# LautIO.net
KiCad netlist of a schematic drawn in EAGLE
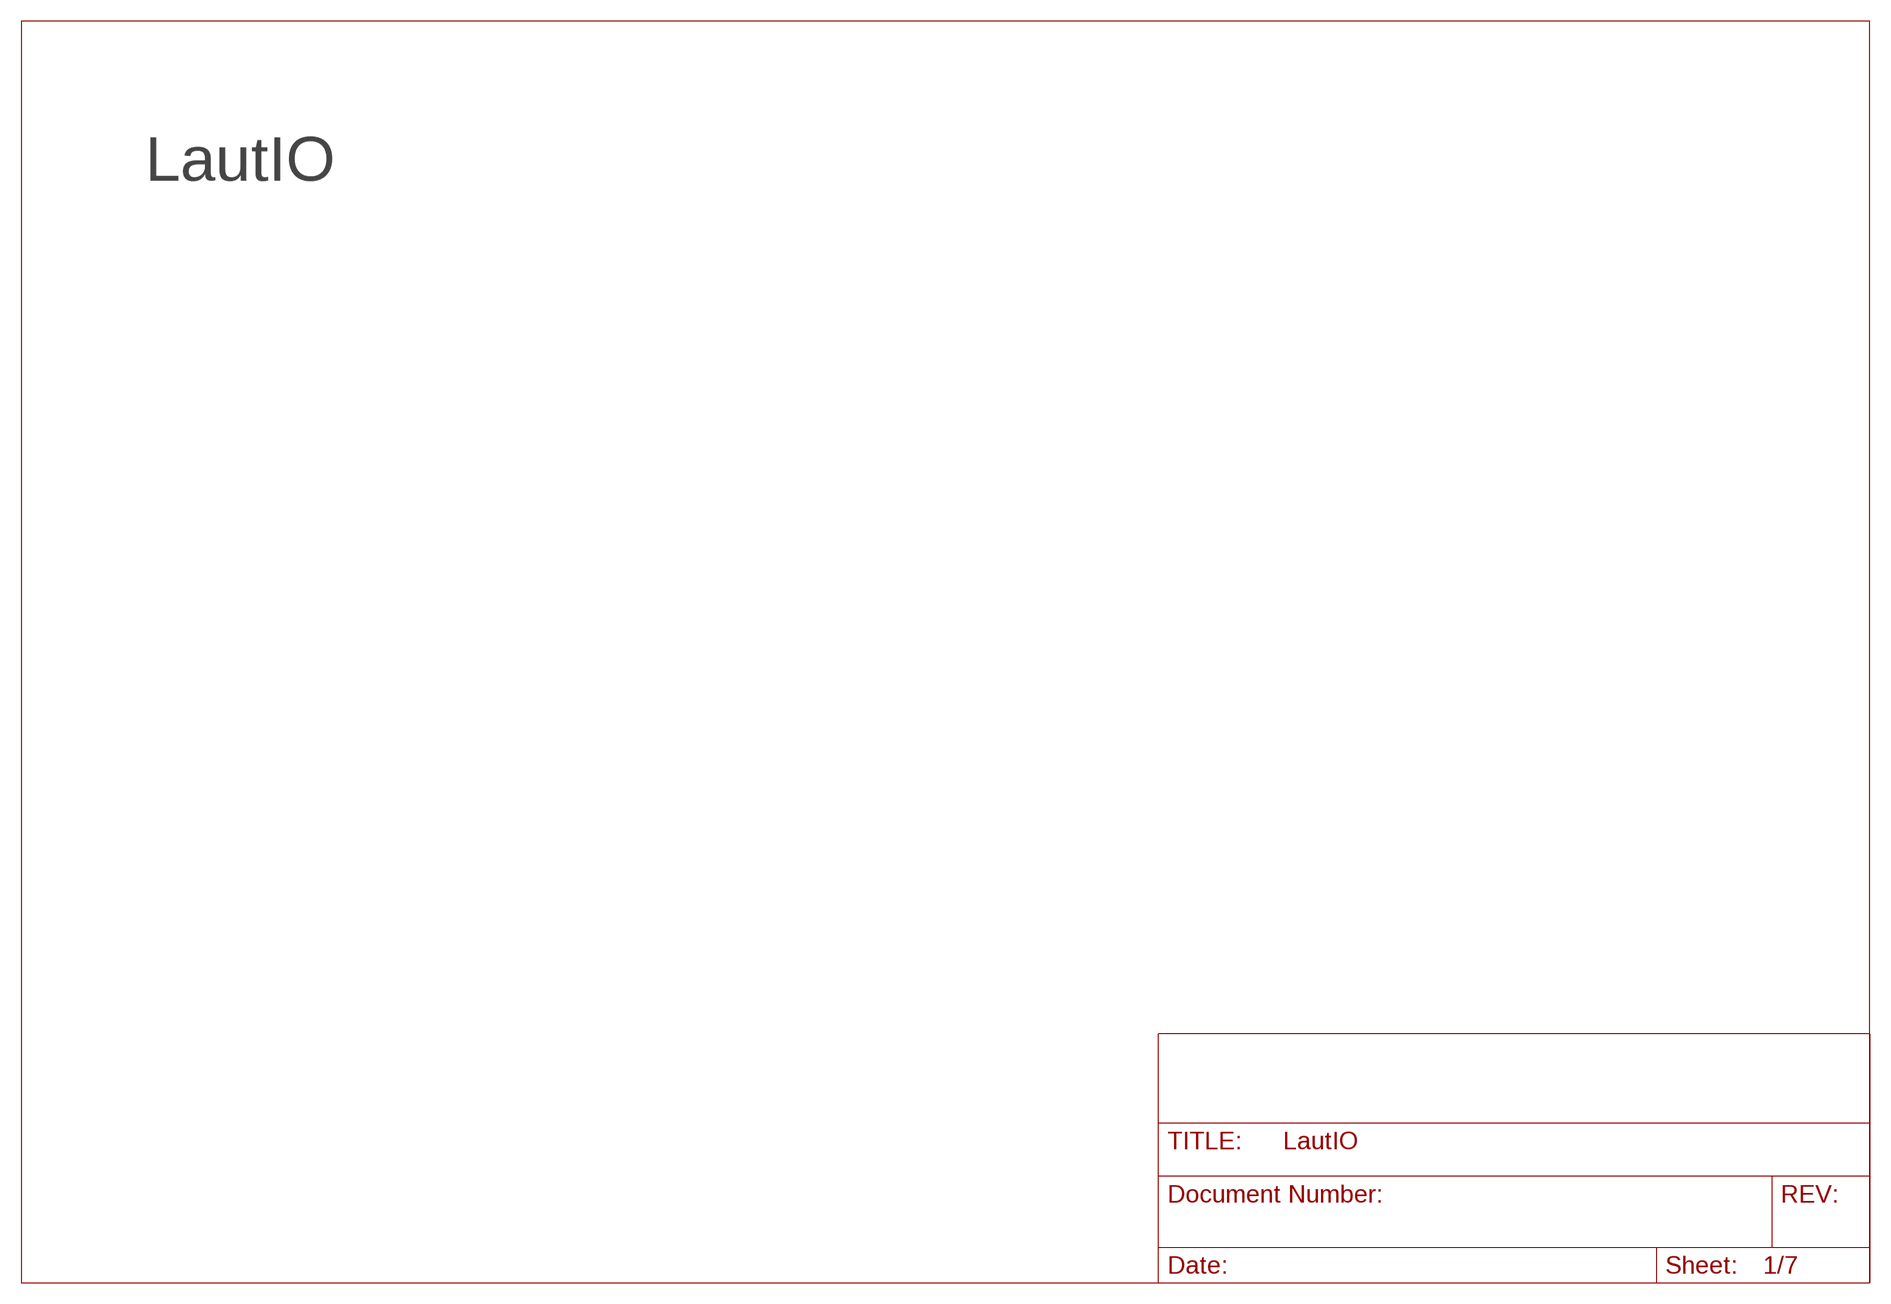
[diagram p0: schematic, sheet 1]
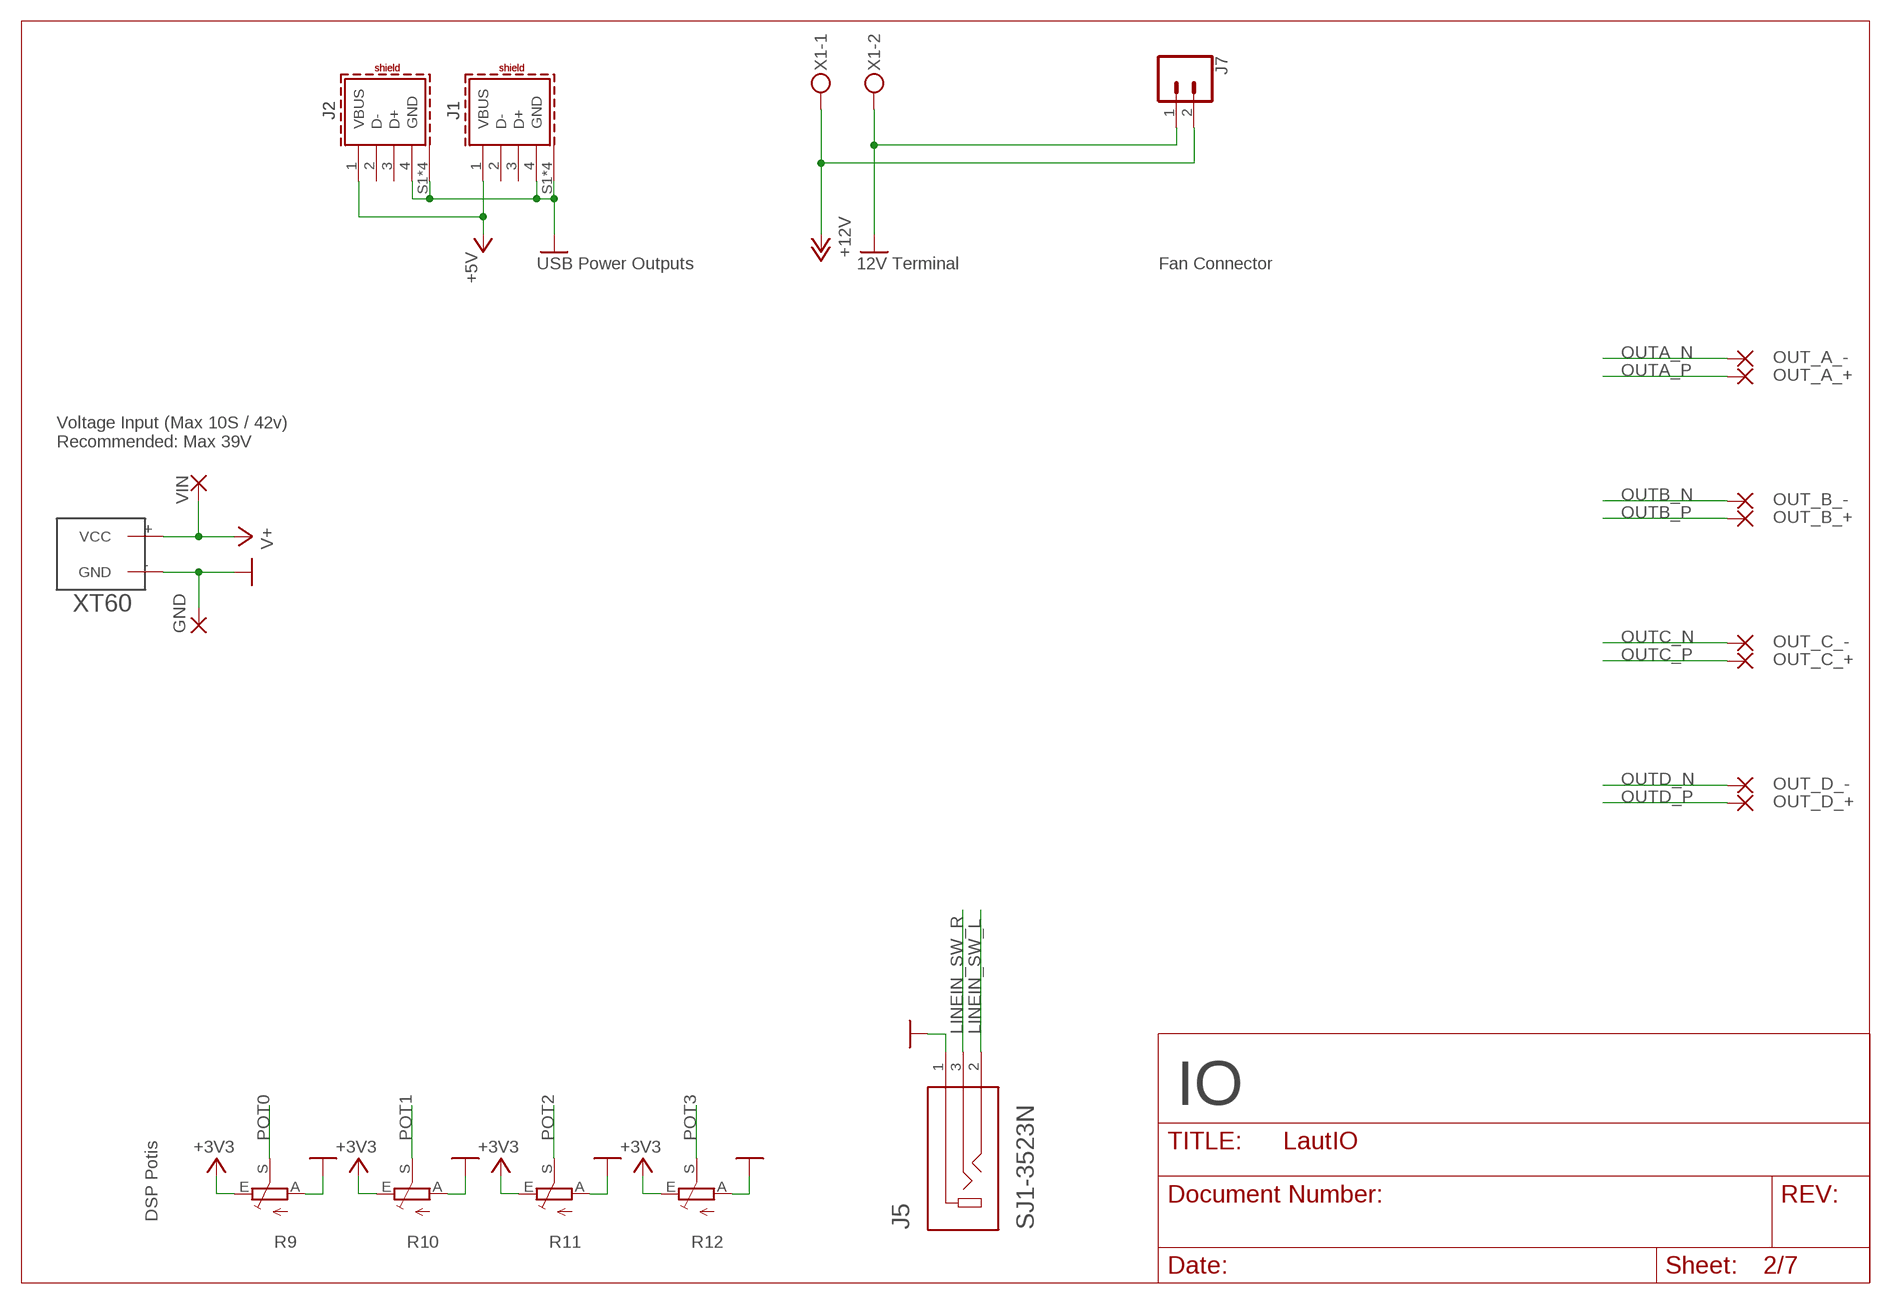
[diagram p1: schematic, sheet 2]
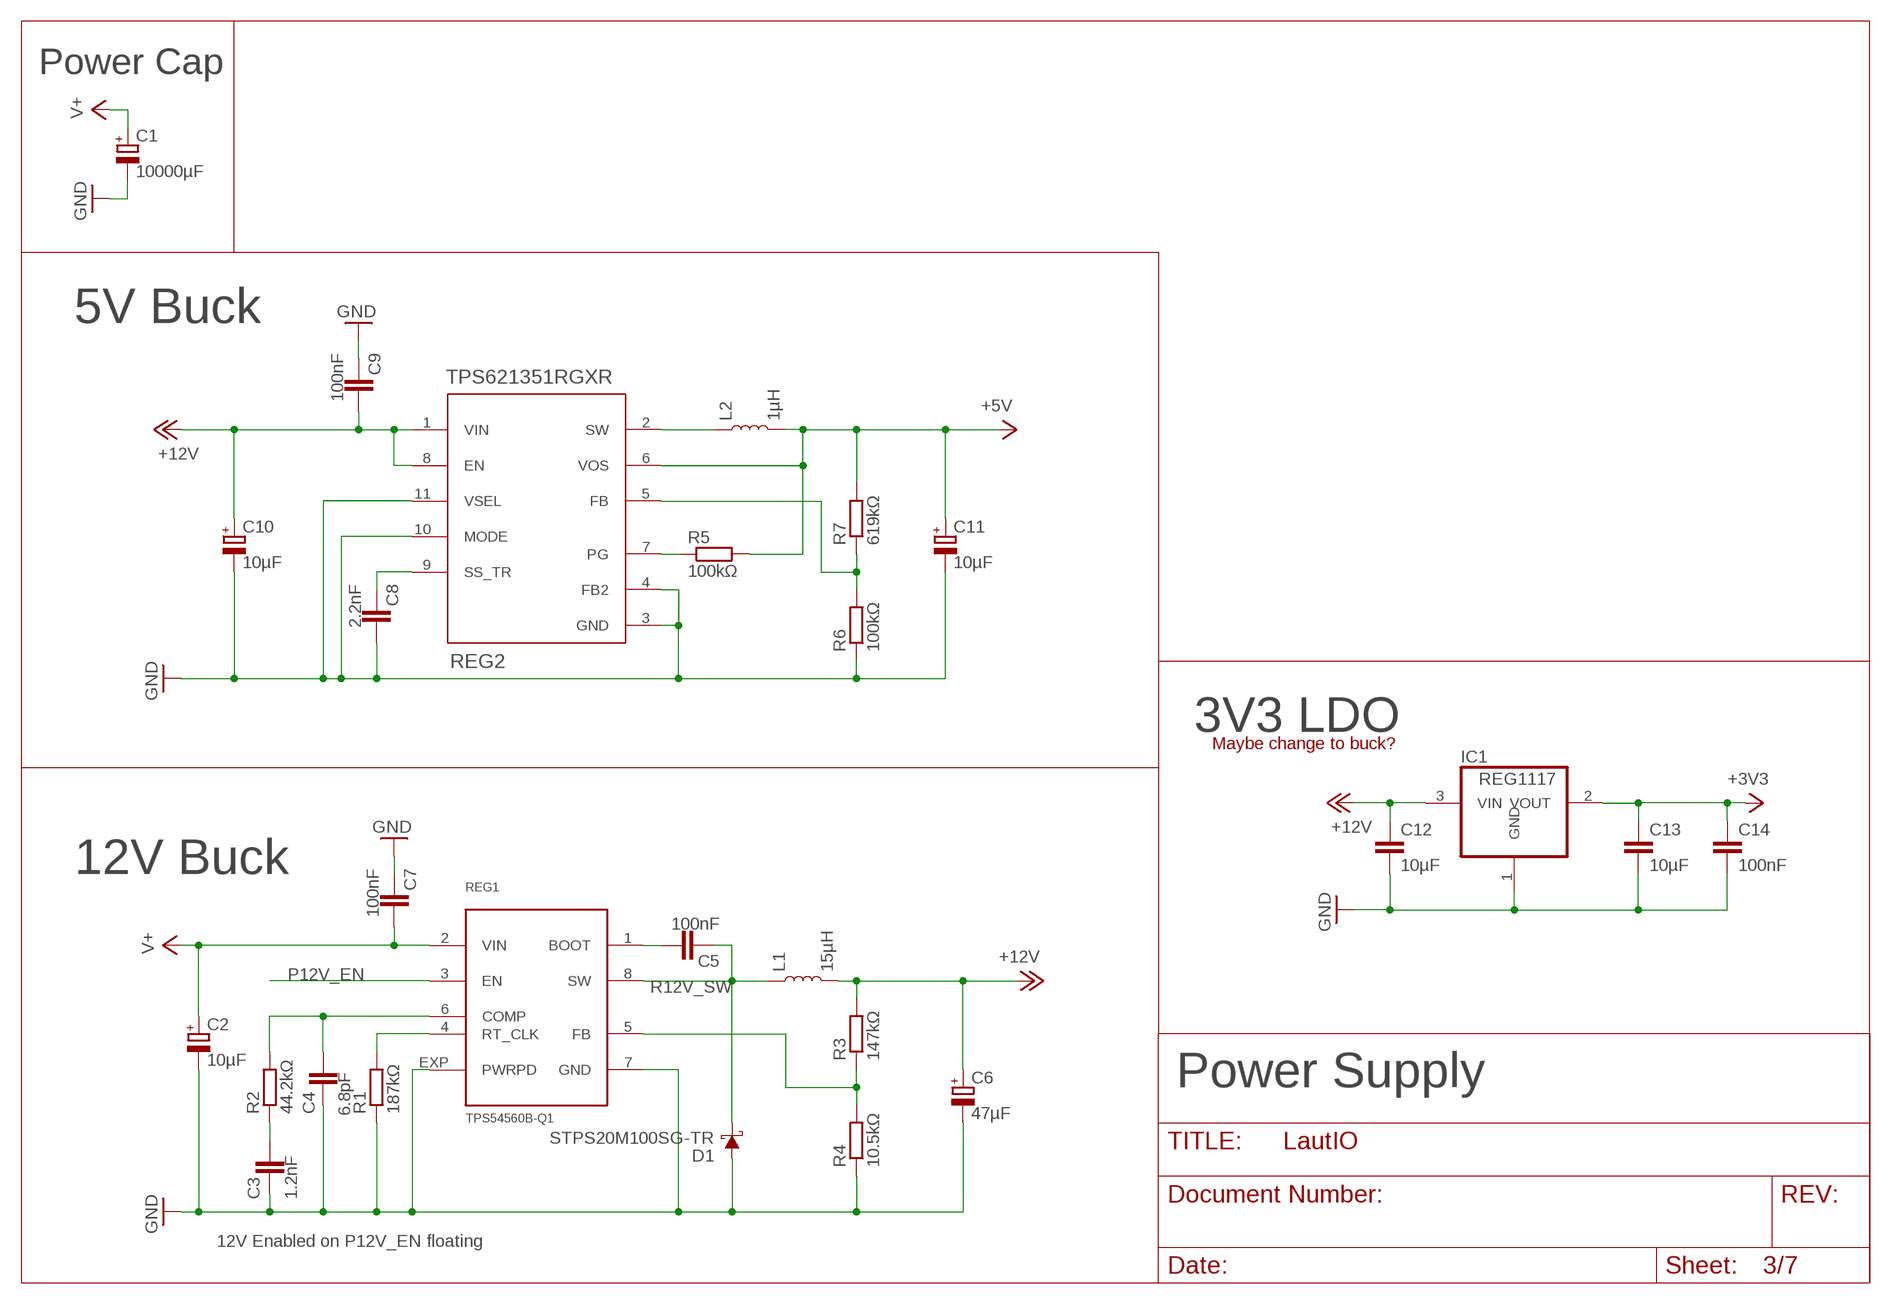
[diagram p2: schematic, sheet 3]
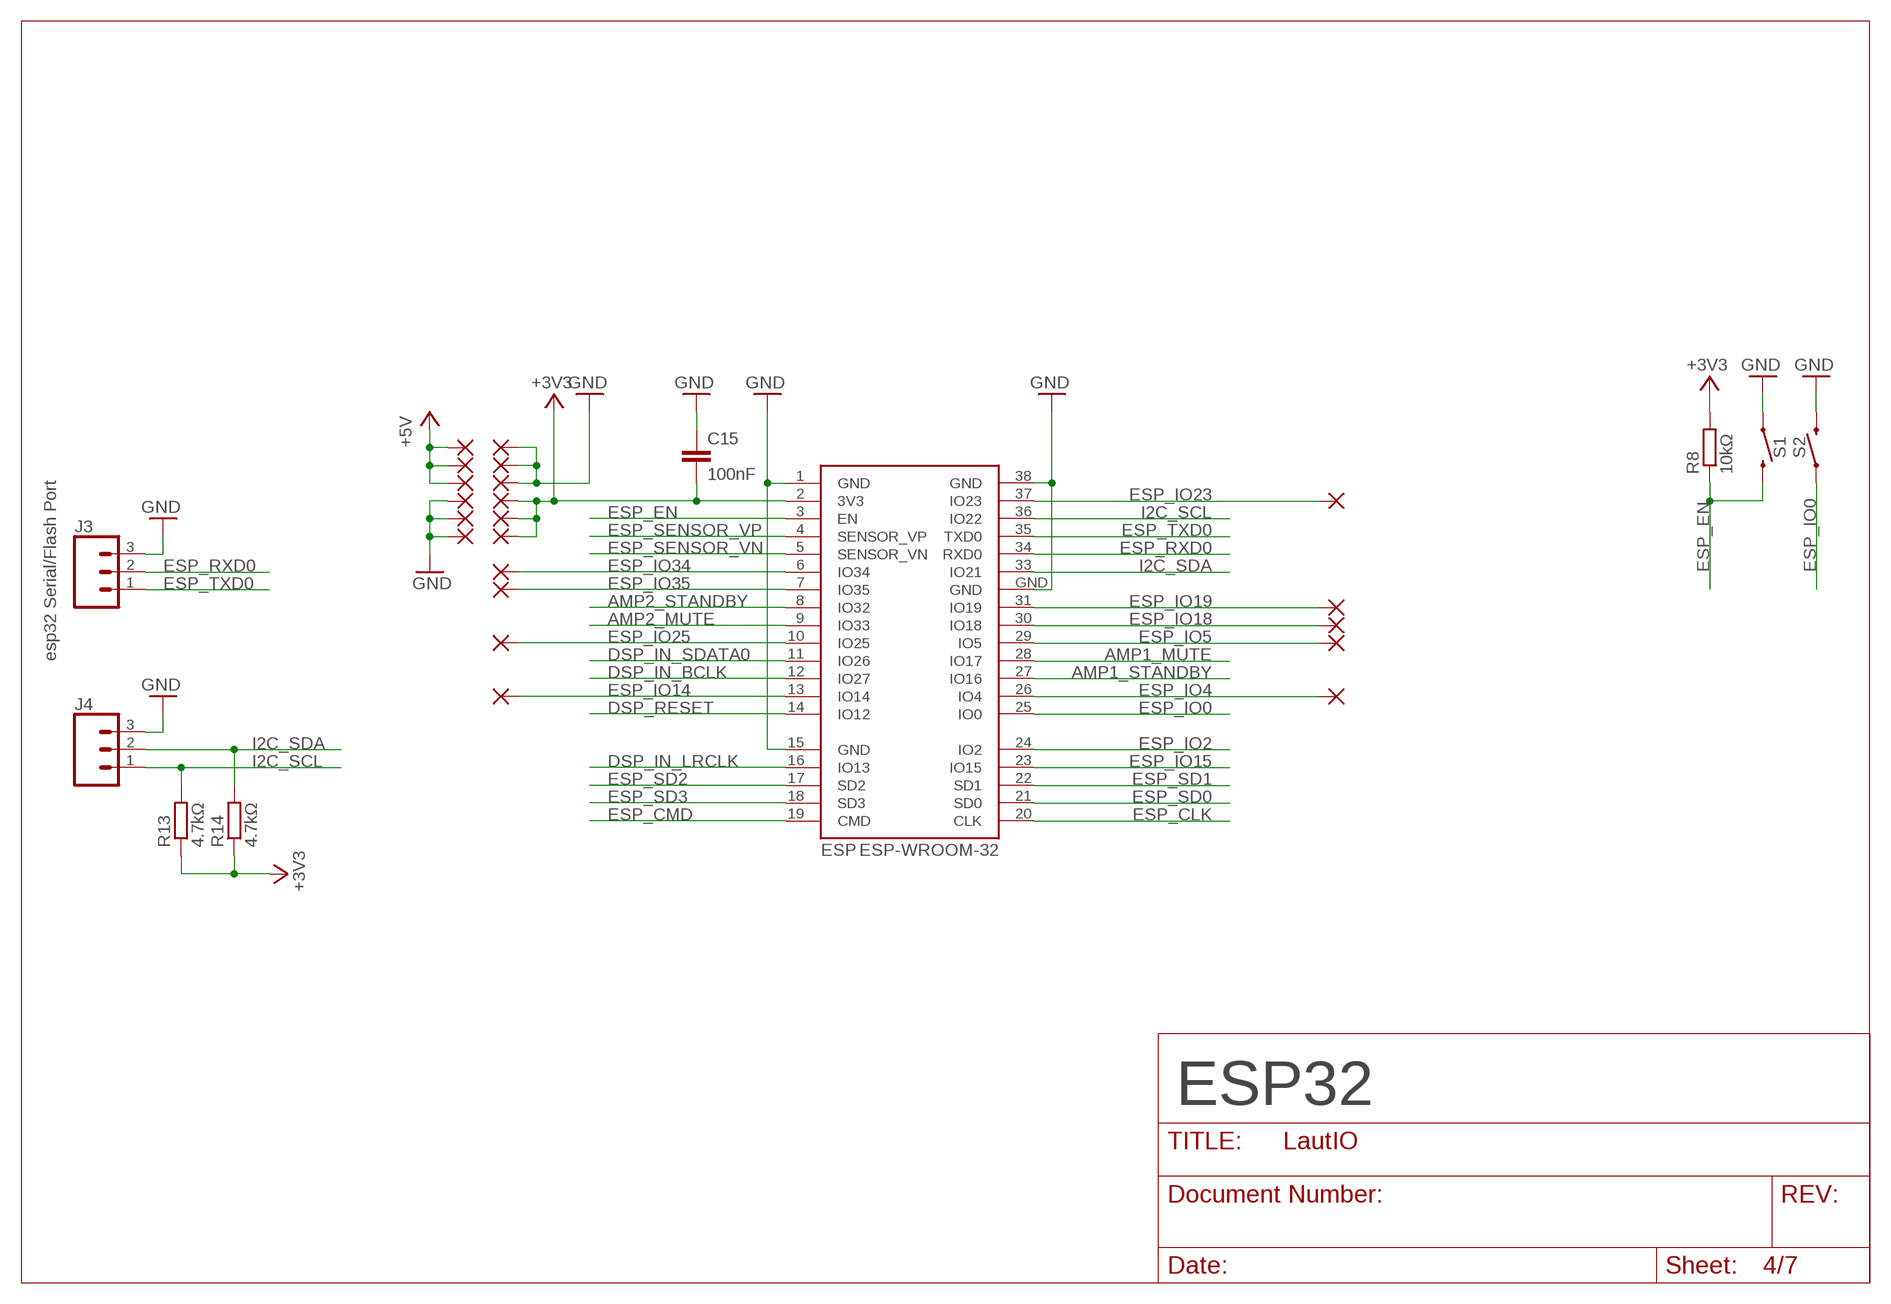
[diagram p3: schematic, sheet 4]
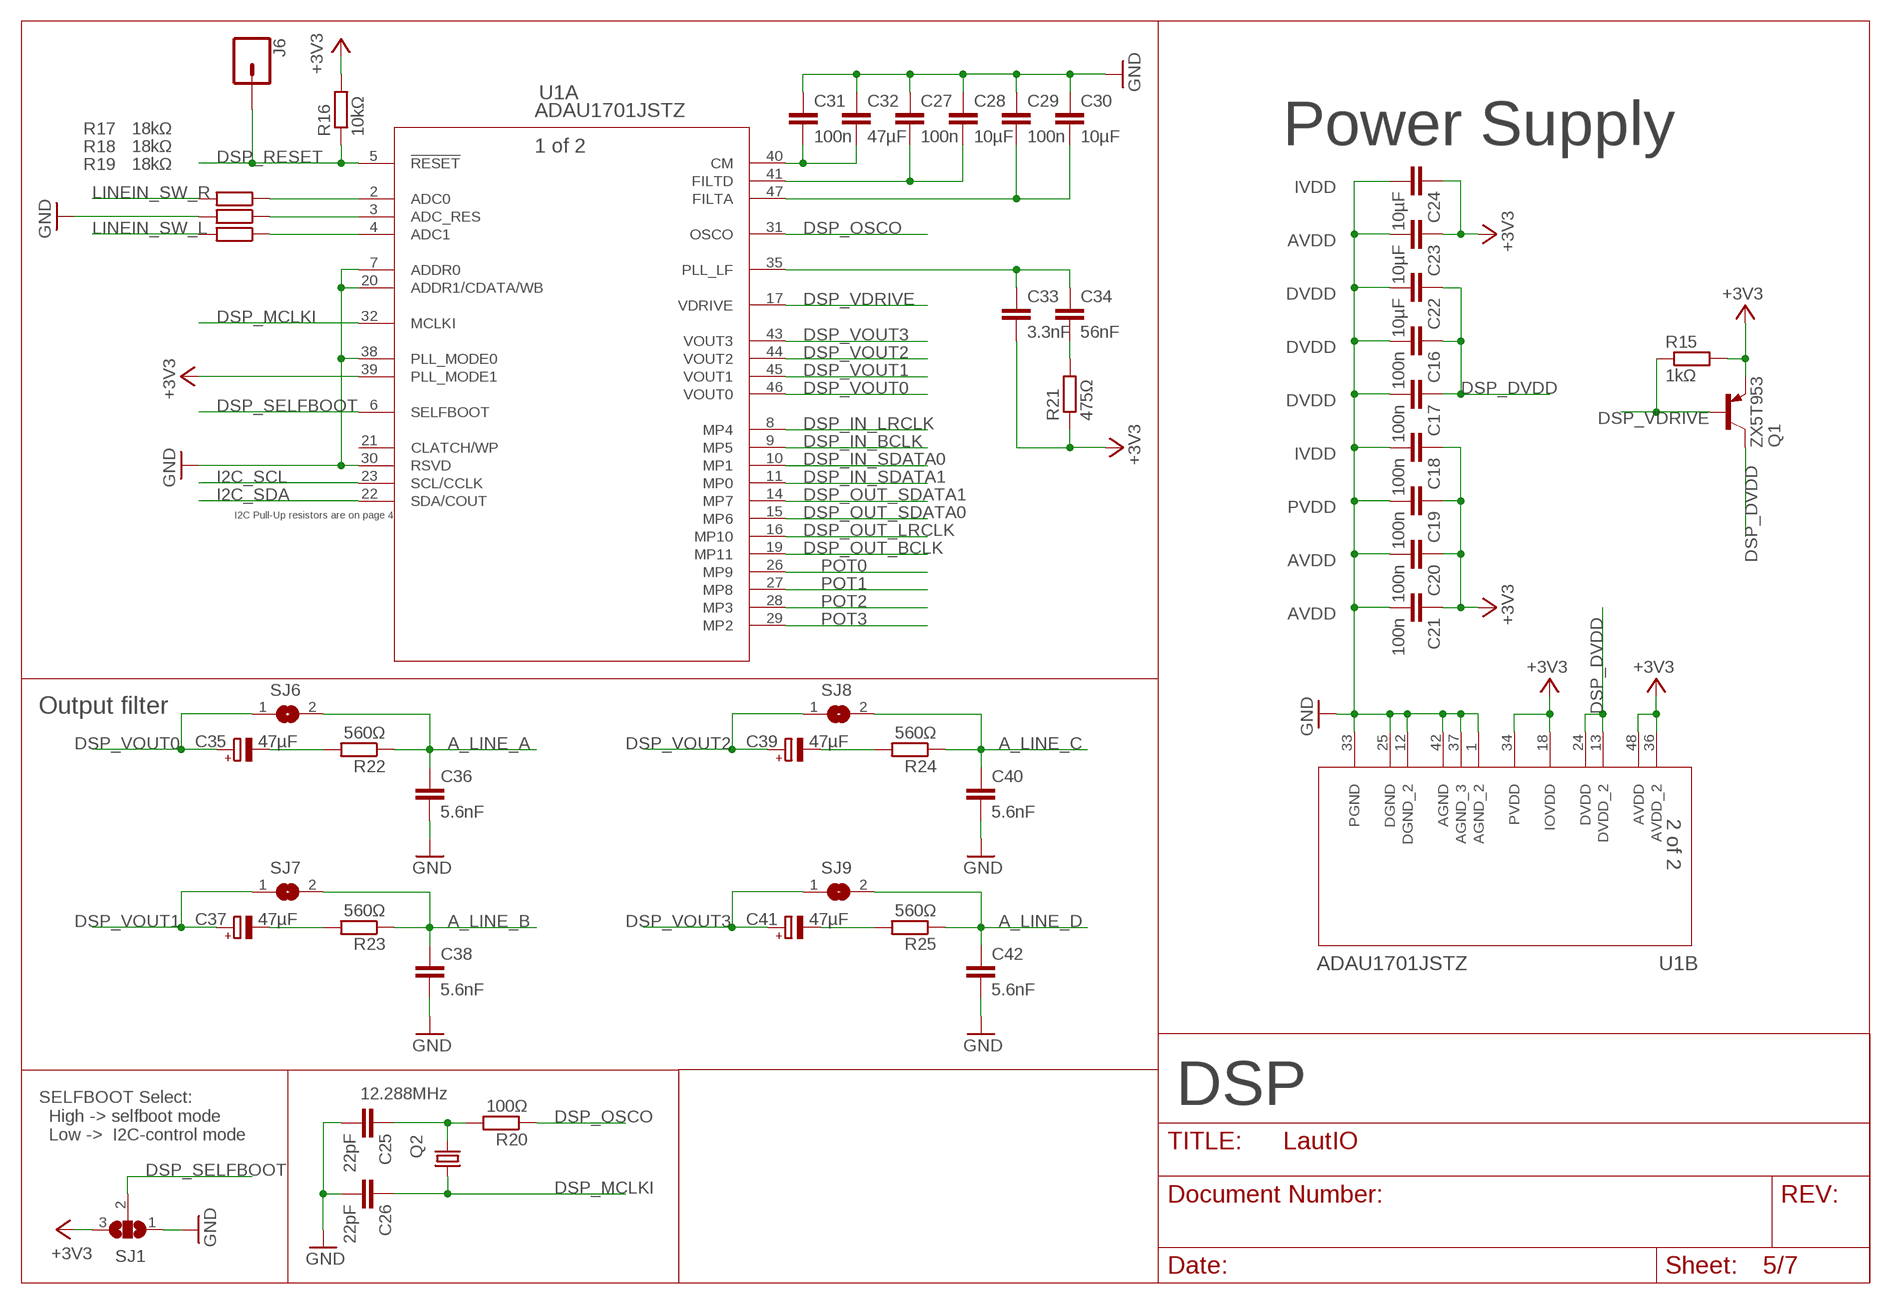
[diagram p4: schematic, sheet 5]
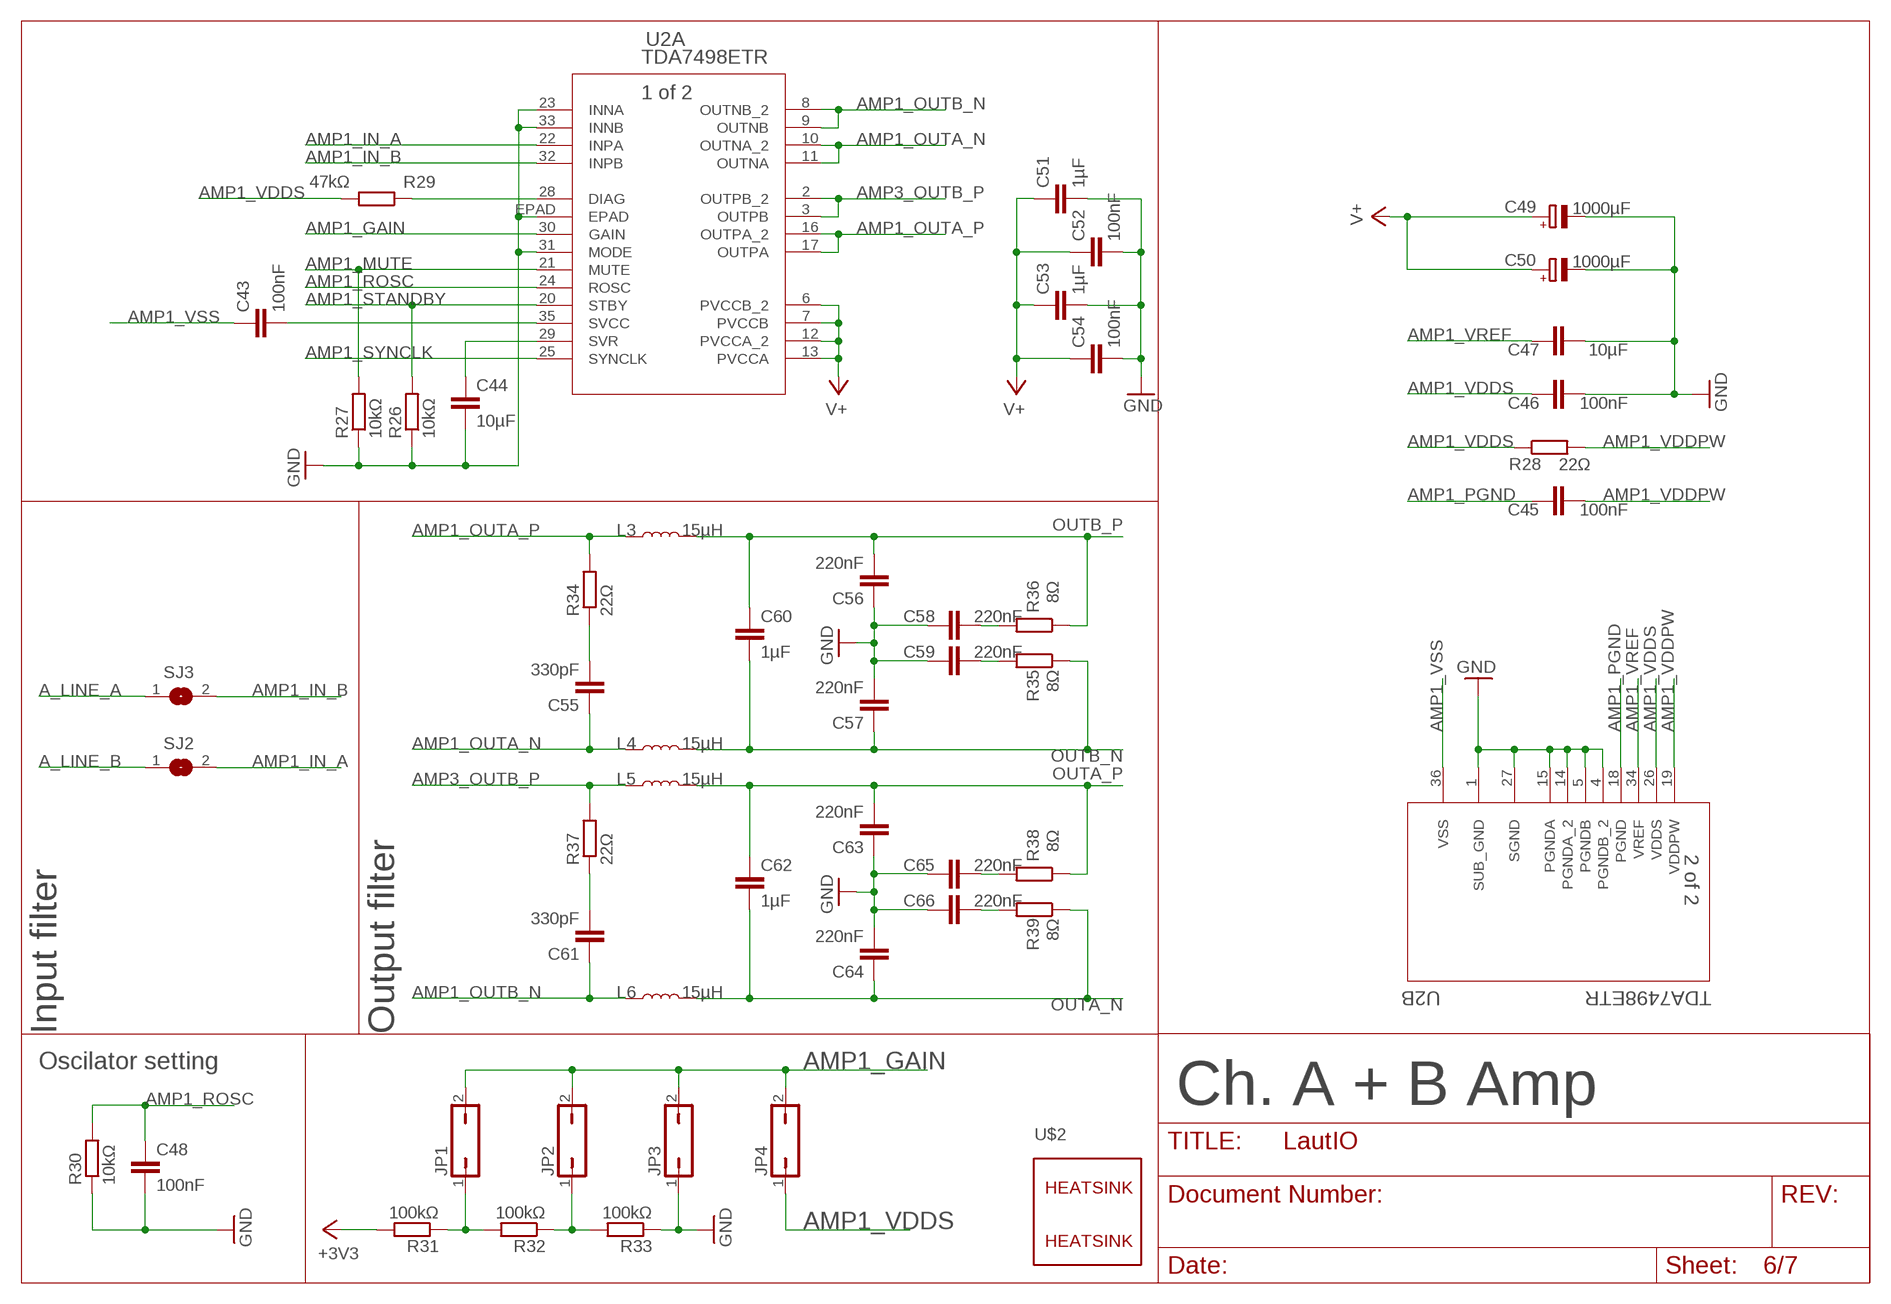
[diagram p5: schematic, sheet 6]
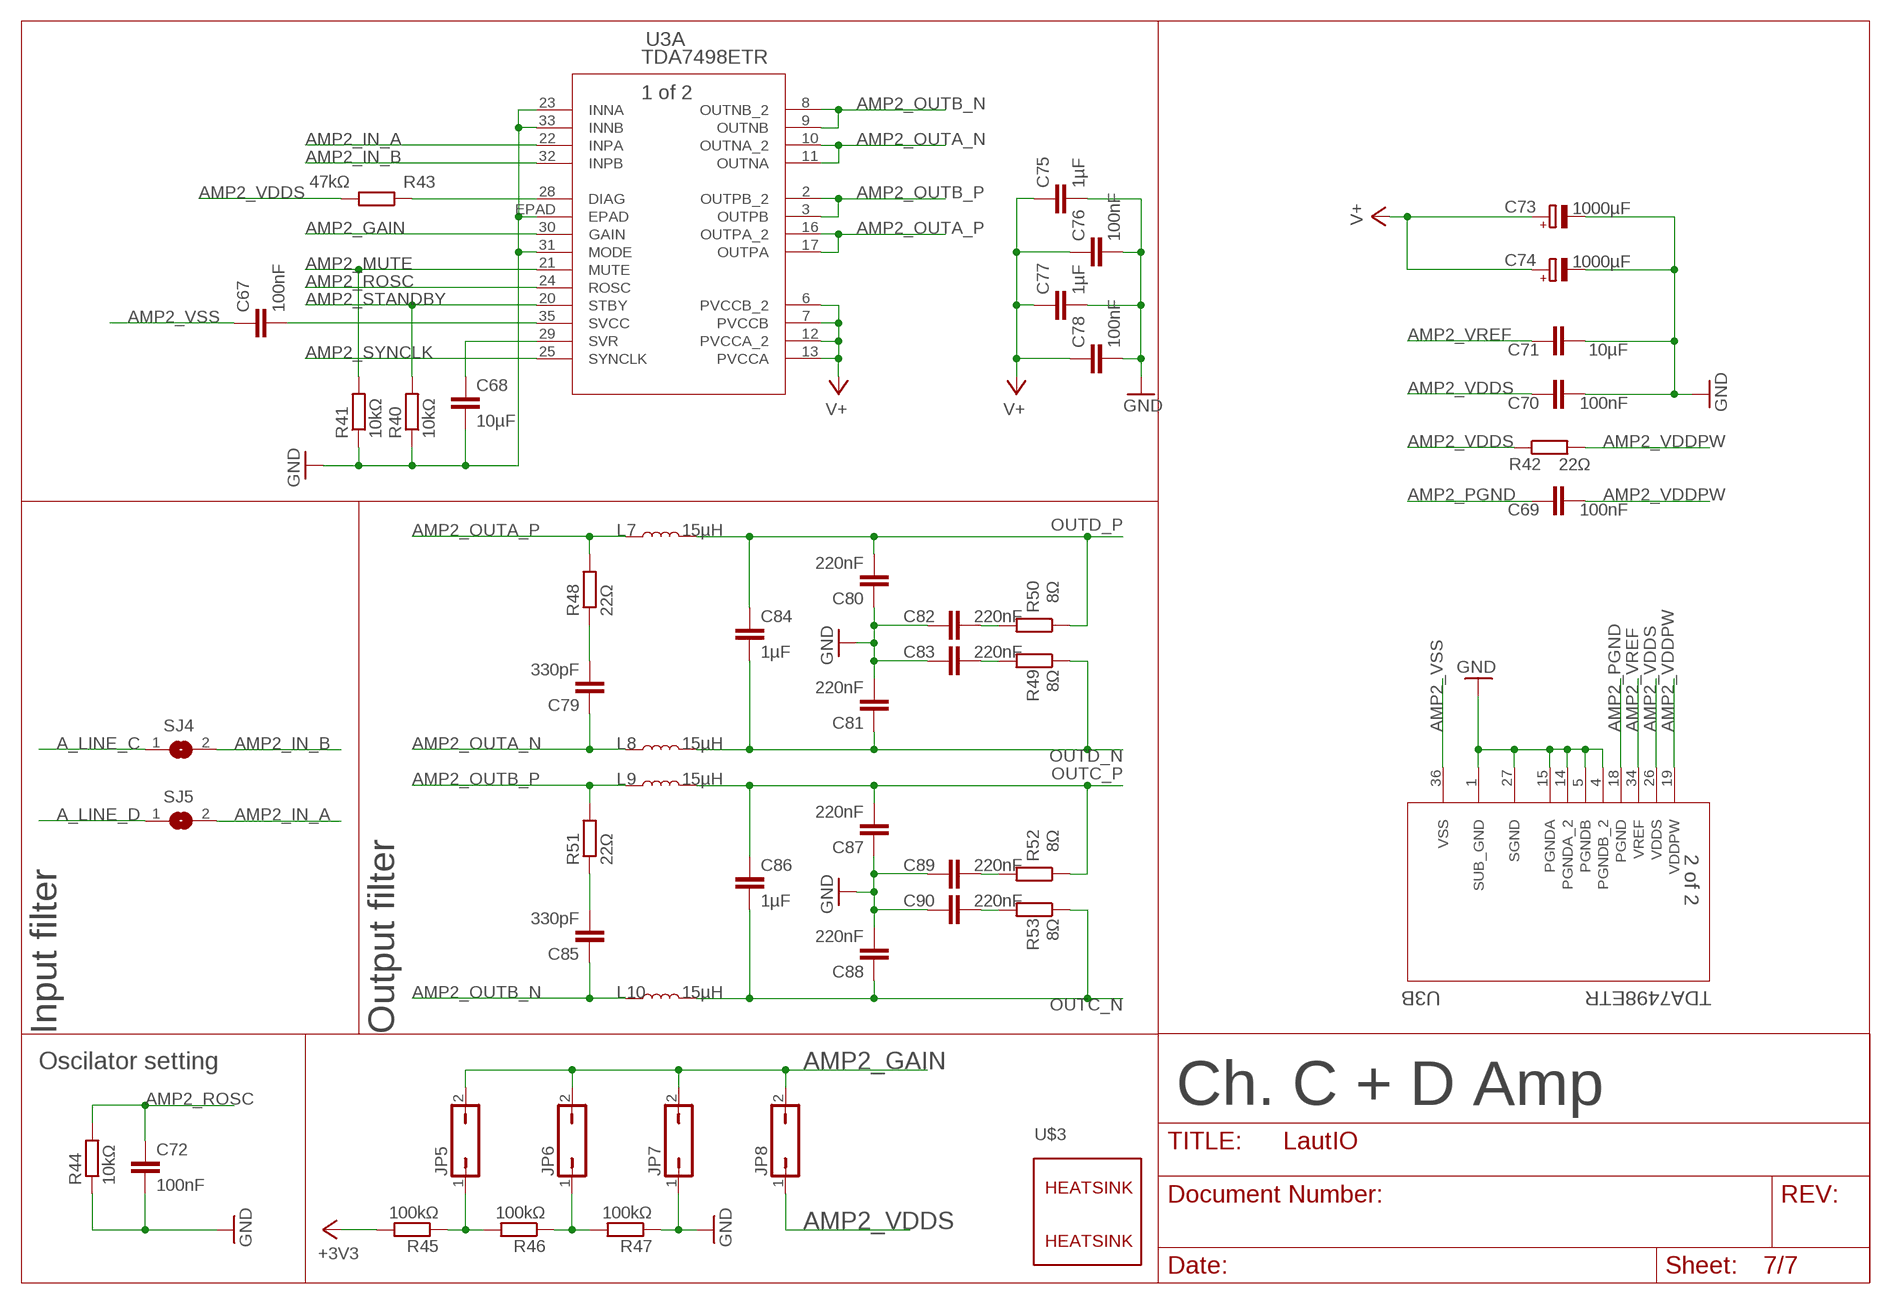
[diagram p6: schematic, sheet 7]

(export (version "E")
  (design (tool "Eeschema 10.0.6"))
  (components
    (comp (ref "C15")
      (value "100nF")
      (footprint "eagle-import:C0603")
      (libsource (lib "eagle-import") (part "C-EUC0603"))
    )
    (comp (ref "ESP")
      (value "ESP-WROOM-32")
      (footprint "eagle-import:ESP-WROOM-32")
      (libsource (lib "eagle-import") (part "ESP-WROOM-32"))
    )
    (comp (ref "IO4")
      (value "SMD2")
      (footprint "eagle-import:SMD1,27-2,54")
      (libsource (lib "eagle-import") (part "SMD2"))
    )
    (comp (ref "IO5")
      (value "SMD2")
      (footprint "eagle-import:SMD1,27-2,54")
      (libsource (lib "eagle-import") (part "SMD2"))
    )
    (comp (ref "IO14")
      (value "SMD2")
      (footprint "eagle-import:SMD1,27-2,54")
      (libsource (lib "eagle-import") (part "SMD2"))
    )
    (comp (ref "IO18")
      (value "SMD2")
      (footprint "eagle-import:SMD1,27-2,54")
      (libsource (lib "eagle-import") (part "SMD2"))
    )
    (comp (ref "IO19")
      (value "SMD2")
      (footprint "eagle-import:SMD1,27-2,54")
      (libsource (lib "eagle-import") (part "SMD2"))
    )
    (comp (ref "IO23")
      (value "SMD2")
      (footprint "eagle-import:SMD1,27-2,54")
      (libsource (lib "eagle-import") (part "SMD2"))
    )
    (comp (ref "IO25")
      (value "SMD2")
      (footprint "eagle-import:SMD1,27-2,54")
      (libsource (lib "eagle-import") (part "SMD2"))
    )
    (comp (ref "IO34")
      (value "SMD2")
      (footprint "eagle-import:SMD1,27-2,54")
      (libsource (lib "eagle-import") (part "SMD2"))
    )
    (comp (ref "IO35")
      (value "SMD2")
      (footprint "eagle-import:SMD1,27-2,54")
      (libsource (lib "eagle-import") (part "SMD2"))
    )
    (comp (ref "J3")
      (value "455-1750-1-ND")
      (footprint "eagle-import:1X03")
      (libsource (lib "eagle-import") (part "CONN_03"))
    )
    (comp (ref "J4")
      (value "455-1750-1-ND")
      (footprint "eagle-import:1X03")
      (libsource (lib "eagle-import") (part "CONN_03"))
    )
    (comp (ref "PAD1")
      (value "SMD2")
      (footprint "eagle-import:SMD1,27-2,54")
      (libsource (lib "eagle-import") (part "SMD2"))
    )
    (comp (ref "PAD2")
      (value "SMD2")
      (footprint "eagle-import:SMD1,27-2,54")
      (libsource (lib "eagle-import") (part "SMD2"))
    )
    (comp (ref "PAD3")
      (value "SMD2")
      (footprint "eagle-import:SMD1,27-2,54")
      (libsource (lib "eagle-import") (part "SMD2"))
    )
    (comp (ref "PAD4")
      (value "SMD2")
      (footprint "eagle-import:SMD1,27-2,54")
      (libsource (lib "eagle-import") (part "SMD2"))
    )
    (comp (ref "PAD5")
      (value "SMD2")
      (footprint "eagle-import:SMD1,27-2,54")
      (libsource (lib "eagle-import") (part "SMD2"))
    )
    (comp (ref "PAD6")
      (value "SMD2")
      (footprint "eagle-import:SMD1,27-2,54")
      (libsource (lib "eagle-import") (part "SMD2"))
    )
    (comp (ref "PAD7")
      (value "SMD2")
      (footprint "eagle-import:SMD1,27-2,54")
      (libsource (lib "eagle-import") (part "SMD2"))
    )
    (comp (ref "PAD8")
      (value "SMD2")
      (footprint "eagle-import:SMD1,27-2,54")
      (libsource (lib "eagle-import") (part "SMD2"))
    )
    (comp (ref "PAD9")
      (value "SMD2")
      (footprint "eagle-import:SMD1,27-2,54")
      (libsource (lib "eagle-import") (part "SMD2"))
    )
    (comp (ref "PAD10")
      (value "SMD2")
      (footprint "eagle-import:SMD1,27-2,54")
      (libsource (lib "eagle-import") (part "SMD2"))
    )
    (comp (ref "PAD11")
      (value "SMD2")
      (footprint "eagle-import:SMD1,27-2,54")
      (libsource (lib "eagle-import") (part "SMD2"))
    )
    (comp (ref "PAD12")
      (value "SMD2")
      (footprint "eagle-import:SMD1,27-2,54")
      (libsource (lib "eagle-import") (part "SMD2"))
    )
    (comp (ref "R8")
      (value "10kΩ")
      (footprint "eagle-import:R0603")
      (libsource (lib "eagle-import") (part "R-EU_R0603"))
    )
    (comp (ref "R13")
      (value "4.7kΩ")
      (footprint "eagle-import:R0603")
      (libsource (lib "eagle-import") (part "R-EU_R0603"))
    )
    (comp (ref "R14")
      (value "4.7kΩ")
      (footprint "eagle-import:R0603")
      (libsource (lib "eagle-import") (part "R-EU_R0603"))
    )
    (comp (ref "S1")
      (value "MOMENTARY-SWITCH-SPST-SMD-6.2MM-TALL")
      (footprint "eagle-import:TACTILE_SWITCH_SMD_6.2MM_TALL")
      (libsource (lib "eagle-import") (part "MOMENTARY-SWITCH-SPST-SMD-6.2MM-TALL"))
    )
    (comp (ref "S2")
      (value "MOMENTARY-SWITCH-SPST-SMD-6.2MM-TALL")
      (footprint "eagle-import:TACTILE_SWITCH_SMD_6.2MM_TALL")
      (libsource (lib "eagle-import") (part "MOMENTARY-SWITCH-SPST-SMD-6.2MM-TALL"))
    )
    (comp (ref "C67")
      (value "100nF")
      (footprint "eagle-import:C0603")
      (libsource (lib "eagle-import") (part "C-EUC0603"))
    )
    (comp (ref "C68")
      (value "10µF")
      (footprint "eagle-import:C1206K")
      (libsource (lib "eagle-import") (part "C-EUC1206K"))
    )
    (comp (ref "C69")
      (value "100nF")
      (footprint "eagle-import:C0603")
      (libsource (lib "eagle-import") (part "C-EUC0603"))
    )
    (comp (ref "C70")
      (value "100nF")
      (footprint "eagle-import:C0603")
      (libsource (lib "eagle-import") (part "C-EUC0603"))
    )
    (comp (ref "C71")
      (value "10µF")
      (footprint "eagle-import:C1206K")
      (libsource (lib "eagle-import") (part "C-EUC1206K"))
    )
    (comp (ref "C72")
      (value "100nF")
      (footprint "eagle-import:C0603")
      (libsource (lib "eagle-import") (part "C-EUC0603"))
    )
    (comp (ref "C73")
      (value "1000µF")
      (footprint "eagle-import:E7,5-16")
      (libsource (lib "eagle-import") (part "CPOL-EUE7.5-16"))
    )
    (comp (ref "C74")
      (value "1000µF")
      (footprint "eagle-import:E7,5-16")
      (libsource (lib "eagle-import") (part "CPOL-EUE7.5-16"))
    )
    (comp (ref "C75")
      (value "1µF")
      (footprint "eagle-import:C0603")
      (libsource (lib "eagle-import") (part "C-EUC0603"))
    )
    (comp (ref "C76")
      (value "100nF")
      (footprint "eagle-import:C0603")
      (libsource (lib "eagle-import") (part "C-EUC0603"))
    )
    (comp (ref "C77")
      (value "1µF")
      (footprint "eagle-import:C0603")
      (libsource (lib "eagle-import") (part "C-EUC0603"))
    )
    (comp (ref "C78")
      (value "100nF")
      (footprint "eagle-import:C0603")
      (libsource (lib "eagle-import") (part "C-EUC0603"))
    )
    (comp (ref "C79")
      (value "330pF")
      (footprint "eagle-import:C0603")
      (libsource (lib "eagle-import") (part "C-EUC0603"))
    )
    (comp (ref "C80")
      (value "220nF")
      (footprint "eagle-import:C0603")
      (libsource (lib "eagle-import") (part "C-EUC0603"))
    )
    (comp (ref "C81")
      (value "220nF")
      (footprint "eagle-import:C0603")
      (libsource (lib "eagle-import") (part "C-EUC0603"))
    )
    (comp (ref "C82")
      (value "220nF")
      (footprint "eagle-import:C0603")
      (libsource (lib "eagle-import") (part "C-EUC0603"))
    )
    (comp (ref "C83")
      (value "220nF")
      (footprint "eagle-import:C0603")
      (libsource (lib "eagle-import") (part "C-EUC0603"))
    )
    (comp (ref "C84")
      (value "1µF")
      (footprint "eagle-import:C3640")
      (libsource (lib "eagle-import") (part "C-EUC3640"))
    )
    (comp (ref "C85")
      (value "330pF")
      (footprint "eagle-import:C0603")
      (libsource (lib "eagle-import") (part "C-EUC0603"))
    )
    (comp (ref "C86")
      (value "1µF")
      (footprint "eagle-import:C3640")
      (libsource (lib "eagle-import") (part "C-EUC3640"))
    )
    (comp (ref "C87")
      (value "220nF")
      (footprint "eagle-import:C0603")
      (libsource (lib "eagle-import") (part "C-EUC0603"))
    )
    (comp (ref "C88")
      (value "220nF")
      (footprint "eagle-import:C0603")
      (libsource (lib "eagle-import") (part "C-EUC0603"))
    )
    (comp (ref "C89")
      (value "220nF")
      (footprint "eagle-import:C0603")
      (libsource (lib "eagle-import") (part "C-EUC0603"))
    )
    (comp (ref "C90")
      (value "220nF")
      (footprint "eagle-import:C0603")
      (libsource (lib "eagle-import") (part "C-EUC0603"))
    )
    (comp (ref "JP5")
      (value "JP1Q")
      (footprint "eagle-import:JP1")
      (libsource (lib "eagle-import") (part "JP1Q"))
    )
    (comp (ref "JP6")
      (value "JP1Q")
      (footprint "eagle-import:JP1")
      (libsource (lib "eagle-import") (part "JP1Q"))
    )
    (comp (ref "JP7")
      (value "JP1Q")
      (footprint "eagle-import:JP1")
      (libsource (lib "eagle-import") (part "JP1Q"))
    )
    (comp (ref "JP8")
      (value "JP1Q")
      (footprint "eagle-import:JP1")
      (libsource (lib "eagle-import") (part "JP1Q"))
    )
    (comp (ref "L7")
      (value "15µH")
      (footprint "eagle-import:INDUCTOR_SDR1307")
      (libsource (lib "eagle-import") (part "INDUCTOR-SDR13-27UH"))
    )
    (comp (ref "L8")
      (value "15µH")
      (footprint "eagle-import:INDUCTOR_SDR1307")
      (libsource (lib "eagle-import") (part "INDUCTOR-SDR13-27UH"))
    )
    (comp (ref "L9")
      (value "15µH")
      (footprint "eagle-import:INDUCTOR_SDR1307")
      (libsource (lib "eagle-import") (part "INDUCTOR-SDR13-27UH"))
    )
    (comp (ref "L10")
      (value "15µH")
      (footprint "eagle-import:INDUCTOR_SDR1307")
      (libsource (lib "eagle-import") (part "INDUCTOR-SDR13-27UH"))
    )
    (comp (ref "R40")
      (value "10kΩ")
      (footprint "eagle-import:R0603")
      (libsource (lib "eagle-import") (part "R-EU_R0603"))
    )
    (comp (ref "R41")
      (value "10kΩ")
      (footprint "eagle-import:R0603")
      (libsource (lib "eagle-import") (part "R-EU_R0603"))
    )
    (comp (ref "R42")
      (value "22Ω")
      (footprint "eagle-import:R0603")
      (libsource (lib "eagle-import") (part "R-EU_R0603"))
    )
    (comp (ref "R43")
      (value "47kΩ")
      (footprint "eagle-import:R0603")
      (libsource (lib "eagle-import") (part "R-EU_R0603"))
    )
    (comp (ref "R44")
      (value "10kΩ")
      (footprint "eagle-import:R0603")
      (libsource (lib "eagle-import") (part "R-EU_R0603"))
    )
    (comp (ref "R45")
      (value "100kΩ")
      (footprint "eagle-import:R0603")
      (libsource (lib "eagle-import") (part "R-EU_R0603"))
    )
    (comp (ref "R46")
      (value "100kΩ")
      (footprint "eagle-import:R0603")
      (libsource (lib "eagle-import") (part "R-EU_R0603"))
    )
    (comp (ref "R47")
      (value "100kΩ")
      (footprint "eagle-import:R0603")
      (libsource (lib "eagle-import") (part "R-EU_R0603"))
    )
    (comp (ref "R48")
      (value "22Ω")
      (footprint "eagle-import:R0603")
      (libsource (lib "eagle-import") (part "R-EU_R0603"))
    )
    (comp (ref "R49")
      (value "8Ω")
      (footprint "eagle-import:R0603")
      (libsource (lib "eagle-import") (part "R-EU_R0603"))
    )
    (comp (ref "R50")
      (value "8Ω")
      (footprint "eagle-import:R0603")
      (libsource (lib "eagle-import") (part "R-EU_R0603"))
    )
    (comp (ref "R51")
      (value "22Ω")
      (footprint "eagle-import:R0603")
      (libsource (lib "eagle-import") (part "R-EU_R0603"))
    )
    (comp (ref "R52")
      (value "8Ω")
      (footprint "eagle-import:R0603")
      (libsource (lib "eagle-import") (part "R-EU_R0603"))
    )
    (comp (ref "R53")
      (value "8Ω")
      (footprint "eagle-import:R0603")
      (libsource (lib "eagle-import") (part "R-EU_R0603"))
    )
    (comp (ref "SJ4") (value "SJ") (footprint "eagle-import:SJ") (libsource (lib "eagle-import") (part "SJ")))
    (comp (ref "SJ5") (value "SJ") (footprint "eagle-import:SJ") (libsource (lib "eagle-import") (part "SJ")))
    (comp (ref "U$3")
      (value "ATS-CPX030030030")
      (footprint "eagle-import:ATS-CPX030030030")
      (libsource (lib "eagle-import") (part "ATS-CPX030030030"))
    )
    (comp (ref "U3")
      (value "TDA7498ETR")
      (footprint "eagle-import:SSO36_TDA7498ETR_STM")
      (fields (field (name "COPYRIGHT") "Copyright (C) 2018 Accelerated Designs. All rights reserved"))
      (libsource (lib "eagle-import") (part "TDA7498ETR"))
    )
    (comp (ref "C43")
      (value "100nF")
      (footprint "eagle-import:C0603")
      (libsource (lib "eagle-import") (part "C-EUC0603"))
    )
    (comp (ref "C44")
      (value "10µF")
      (footprint "eagle-import:C1206K")
      (libsource (lib "eagle-import") (part "C-EUC1206K"))
    )
    (comp (ref "C45")
      (value "100nF")
      (footprint "eagle-import:C0603")
      (libsource (lib "eagle-import") (part "C-EUC0603"))
    )
    (comp (ref "C46")
      (value "100nF")
      (footprint "eagle-import:C0603")
      (libsource (lib "eagle-import") (part "C-EUC0603"))
    )
    (comp (ref "C47")
      (value "10µF")
      (footprint "eagle-import:C1206K")
      (libsource (lib "eagle-import") (part "C-EUC1206K"))
    )
    (comp (ref "C48")
      (value "100nF")
      (footprint "eagle-import:C0603")
      (libsource (lib "eagle-import") (part "C-EUC0603"))
    )
    (comp (ref "C49")
      (value "1000µF")
      (footprint "eagle-import:E7,5-16")
      (libsource (lib "eagle-import") (part "CPOL-EUE7.5-16"))
    )
    (comp (ref "C50")
      (value "1000µF")
      (footprint "eagle-import:E7,5-16")
      (libsource (lib "eagle-import") (part "CPOL-EUE7.5-16"))
    )
    (comp (ref "C51")
      (value "1µF")
      (footprint "eagle-import:C0603")
      (libsource (lib "eagle-import") (part "C-EUC0603"))
    )
    (comp (ref "C52")
      (value "100nF")
      (footprint "eagle-import:C0603")
      (libsource (lib "eagle-import") (part "C-EUC0603"))
    )
    (comp (ref "C53")
      (value "1µF")
      (footprint "eagle-import:C0603")
      (libsource (lib "eagle-import") (part "C-EUC0603"))
    )
    (comp (ref "C54")
      (value "100nF")
      (footprint "eagle-import:C0603")
      (libsource (lib "eagle-import") (part "C-EUC0603"))
    )
    (comp (ref "C55")
      (value "330pF")
      (footprint "eagle-import:C0603")
      (libsource (lib "eagle-import") (part "C-EUC0603"))
    )
    (comp (ref "C56")
      (value "220nF")
      (footprint "eagle-import:C0603")
      (libsource (lib "eagle-import") (part "C-EUC0603"))
    )
    (comp (ref "C57")
      (value "220nF")
      (footprint "eagle-import:C0603")
      (libsource (lib "eagle-import") (part "C-EUC0603"))
    )
    (comp (ref "C58")
      (value "220nF")
      (footprint "eagle-import:C0603")
      (libsource (lib "eagle-import") (part "C-EUC0603"))
    )
    (comp (ref "C59")
      (value "220nF")
      (footprint "eagle-import:C0603")
      (libsource (lib "eagle-import") (part "C-EUC0603"))
    )
    (comp (ref "C60")
      (value "1µF")
      (footprint "eagle-import:C3640")
      (libsource (lib "eagle-import") (part "C-EUC3640"))
    )
    (comp (ref "C61")
      (value "330pF")
      (footprint "eagle-import:C0603")
      (libsource (lib "eagle-import") (part "C-EUC0603"))
    )
    (comp (ref "C62")
      (value "1µF")
      (footprint "eagle-import:C3640")
      (libsource (lib "eagle-import") (part "C-EUC3640"))
    )
    (comp (ref "C63")
      (value "220nF")
      (footprint "eagle-import:C0603")
      (libsource (lib "eagle-import") (part "C-EUC0603"))
    )
    (comp (ref "C64")
      (value "220nF")
      (footprint "eagle-import:C0603")
      (libsource (lib "eagle-import") (part "C-EUC0603"))
    )
    (comp (ref "C65")
      (value "220nF")
      (footprint "eagle-import:C0603")
      (libsource (lib "eagle-import") (part "C-EUC0603"))
    )
    (comp (ref "C66")
      (value "220nF")
      (footprint "eagle-import:C0603")
      (libsource (lib "eagle-import") (part "C-EUC0603"))
    )
    (comp (ref "JP1")
      (value "JP1Q")
      (footprint "eagle-import:JP1")
      (libsource (lib "eagle-import") (part "JP1Q"))
    )
    (comp (ref "JP2")
      (value "JP1Q")
      (footprint "eagle-import:JP1")
      (libsource (lib "eagle-import") (part "JP1Q"))
    )
    (comp (ref "JP3")
      (value "JP1Q")
      (footprint "eagle-import:JP1")
      (libsource (lib "eagle-import") (part "JP1Q"))
    )
    (comp (ref "JP4")
      (value "JP1Q")
      (footprint "eagle-import:JP1")
      (libsource (lib "eagle-import") (part "JP1Q"))
    )
    (comp (ref "L3")
      (value "15µH")
      (footprint "eagle-import:INDUCTOR_SDR1307")
      (libsource (lib "eagle-import") (part "INDUCTOR-SDR13-27UH"))
    )
    (comp (ref "L4")
      (value "15µH")
      (footprint "eagle-import:INDUCTOR_SDR1307")
      (libsource (lib "eagle-import") (part "INDUCTOR-SDR13-27UH"))
    )
    (comp (ref "L5")
      (value "15µH")
      (footprint "eagle-import:INDUCTOR_SDR1307")
      (libsource (lib "eagle-import") (part "INDUCTOR-SDR13-27UH"))
    )
    (comp (ref "L6")
      (value "15µH")
      (footprint "eagle-import:INDUCTOR_SDR1307")
      (libsource (lib "eagle-import") (part "INDUCTOR-SDR13-27UH"))
    )
    (comp (ref "R26")
      (value "10kΩ")
      (footprint "eagle-import:R0603")
      (libsource (lib "eagle-import") (part "R-EU_R0603"))
    )
    (comp (ref "R27")
      (value "10kΩ")
      (footprint "eagle-import:R0603")
      (libsource (lib "eagle-import") (part "R-EU_R0603"))
    )
    (comp (ref "R28")
      (value "22Ω")
      (footprint "eagle-import:R0603")
      (libsource (lib "eagle-import") (part "R-EU_R0603"))
    )
    (comp (ref "R29")
      (value "47kΩ")
      (footprint "eagle-import:R0603")
      (libsource (lib "eagle-import") (part "R-EU_R0603"))
    )
    (comp (ref "R30")
      (value "10kΩ")
      (footprint "eagle-import:R0603")
      (libsource (lib "eagle-import") (part "R-EU_R0603"))
    )
    (comp (ref "R31")
      (value "100kΩ")
      (footprint "eagle-import:R0603")
      (libsource (lib "eagle-import") (part "R-EU_R0603"))
    )
    (comp (ref "R32")
      (value "100kΩ")
      (footprint "eagle-import:R0603")
      (libsource (lib "eagle-import") (part "R-EU_R0603"))
    )
    (comp (ref "R33")
      (value "100kΩ")
      (footprint "eagle-import:R0603")
      (libsource (lib "eagle-import") (part "R-EU_R0603"))
    )
    (comp (ref "R34")
      (value "22Ω")
      (footprint "eagle-import:R0603")
      (libsource (lib "eagle-import") (part "R-EU_R0603"))
    )
    (comp (ref "R35")
      (value "8Ω")
      (footprint "eagle-import:R0603")
      (libsource (lib "eagle-import") (part "R-EU_R0603"))
    )
    (comp (ref "R36")
      (value "8Ω")
      (footprint "eagle-import:R0603")
      (libsource (lib "eagle-import") (part "R-EU_R0603"))
    )
    (comp (ref "R37")
      (value "22Ω")
      (footprint "eagle-import:R0603")
      (libsource (lib "eagle-import") (part "R-EU_R0603"))
    )
    (comp (ref "R38")
      (value "8Ω")
      (footprint "eagle-import:R0603")
      (libsource (lib "eagle-import") (part "R-EU_R0603"))
    )
    (comp (ref "R39")
      (value "8Ω")
      (footprint "eagle-import:R0603")
      (libsource (lib "eagle-import") (part "R-EU_R0603"))
    )
    (comp (ref "SJ2") (value "SJ") (footprint "eagle-import:SJ") (libsource (lib "eagle-import") (part "SJ")))
    (comp (ref "SJ3") (value "SJ") (footprint "eagle-import:SJ") (libsource (lib "eagle-import") (part "SJ")))
    (comp (ref "U$2")
      (value "ATS-CPX030030030")
      (footprint "eagle-import:ATS-CPX030030030")
      (libsource (lib "eagle-import") (part "ATS-CPX030030030"))
    )
    (comp (ref "U2")
      (value "TDA7498ETR")
      (footprint "eagle-import:SSO36_TDA7498ETR_STM")
      (fields (field (name "COPYRIGHT") "Copyright (C) 2018 Accelerated Designs. All rights reserved"))
      (libsource (lib "eagle-import") (part "TDA7498ETR"))
    )
    (comp (ref "GND")
      (value "SMD5")
      (footprint "eagle-import:SMD2,54-5,08")
      (libsource (lib "eagle-import") (part "SMD5"))
    )
    (comp (ref "J1")
      (value "614004134726")
      (footprint "eagle-import:614004134726")
      (libsource (lib "eagle-import") (part "614004134726"))
    )
    (comp (ref "J2")
      (value "614004134726")
      (footprint "eagle-import:614004134726")
      (libsource (lib "eagle-import") (part "614004134726"))
    )
    (comp (ref "J5")
      (value "SJ1-3523N")
      (footprint "eagle-import:CUI_SJ1-3523N")
      (fields (field (name "MANUFACTURER") "CUI"))
      (libsource (lib "eagle-import") (part "SJ1-3523N"))
    )
    (comp (ref "J7")
      (value "CONN_02")
      (footprint "eagle-import:1X02")
      (libsource (lib "eagle-import") (part "CONN_02"))
    )
    (comp (ref "OUT_A_+")
      (value "SMD2")
      (footprint "eagle-import:SMD1,27-2,54")
      (libsource (lib "eagle-import") (part "SMD2"))
    )
    (comp (ref "OUT_A_-")
      (value "SMD2")
      (footprint "eagle-import:SMD1,27-2,54")
      (libsource (lib "eagle-import") (part "SMD2"))
    )
    (comp (ref "OUT_B_+")
      (value "SMD2")
      (footprint "eagle-import:SMD1,27-2,54")
      (libsource (lib "eagle-import") (part "SMD2"))
    )
    (comp (ref "OUT_B_-")
      (value "SMD2")
      (footprint "eagle-import:SMD1,27-2,54")
      (libsource (lib "eagle-import") (part "SMD2"))
    )
    (comp (ref "OUT_C_+")
      (value "SMD2")
      (footprint "eagle-import:SMD1,27-2,54")
      (libsource (lib "eagle-import") (part "SMD2"))
    )
    (comp (ref "OUT_C_-")
      (value "SMD2")
      (footprint "eagle-import:SMD1,27-2,54")
      (libsource (lib "eagle-import") (part "SMD2"))
    )
    (comp (ref "OUT_D_+")
      (value "SMD2")
      (footprint "eagle-import:SMD1,27-2,54")
      (libsource (lib "eagle-import") (part "SMD2"))
    )
    (comp (ref "OUT_D_-")
      (value "SMD2")
      (footprint "eagle-import:SMD1,27-2,54")
      (libsource (lib "eagle-import") (part "SMD2"))
    )
    (comp (ref "R9")
      (value "TRIM_EU-CIP20C-6MM")
      (footprint "eagle-import:CIP20C-6MM")
      (libsource (lib "eagle-import") (part "TRIM_EU-CIP20C-6MM"))
    )
    (comp (ref "R10")
      (value "TRIM_EU-CIP20C-6MM")
      (footprint "eagle-import:CIP20C-6MM")
      (libsource (lib "eagle-import") (part "TRIM_EU-CIP20C-6MM"))
    )
    (comp (ref "R11")
      (value "TRIM_EU-CIP20C-6MM")
      (footprint "eagle-import:CIP20C-6MM")
      (libsource (lib "eagle-import") (part "TRIM_EU-CIP20C-6MM"))
    )
    (comp (ref "R12")
      (value "TRIM_EU-CIP20C-6MM")
      (footprint "eagle-import:CIP20C-6MM")
      (libsource (lib "eagle-import") (part "TRIM_EU-CIP20C-6MM"))
    )
    (comp (ref "U$1")
      (value "XT60")
      (footprint "eagle-import:XT60")
      (libsource (lib "eagle-import") (part "XT60"))
    )
    (comp (ref "VIN")
      (value "SMD5")
      (footprint "eagle-import:SMD2,54-5,08")
      (libsource (lib "eagle-import") (part "SMD5"))
    )
    (comp (ref "X1")
      (value "MKDSN1,5/2-5,08")
      (footprint "eagle-import:MKDSN1,5_2-5,08")
      (libsource (lib "eagle-import") (part "MKDSN1,5/2-5,08"))
    )
    (comp (ref "C16")
      (value "100n")
      (footprint "eagle-import:C0603")
      (libsource (lib "eagle-import") (part "C-EUC0603"))
    )
    (comp (ref "C17")
      (value "100n")
      (footprint "eagle-import:C0603")
      (libsource (lib "eagle-import") (part "C-EUC0603"))
    )
    (comp (ref "C18")
      (value "100n")
      (footprint "eagle-import:C0603")
      (libsource (lib "eagle-import") (part "C-EUC0603"))
    )
    (comp (ref "C19")
      (value "100n")
      (footprint "eagle-import:C0603")
      (libsource (lib "eagle-import") (part "C-EUC0603"))
    )
    (comp (ref "C20")
      (value "100n")
      (footprint "eagle-import:C0603")
      (libsource (lib "eagle-import") (part "C-EUC0603"))
    )
    (comp (ref "C21")
      (value "100n")
      (footprint "eagle-import:C0603")
      (libsource (lib "eagle-import") (part "C-EUC0603"))
    )
    (comp (ref "C22")
      (value "10µF")
      (footprint "eagle-import:C1206K")
      (libsource (lib "eagle-import") (part "C-EUC1206K"))
    )
    (comp (ref "C23")
      (value "10µF")
      (footprint "eagle-import:C1206K")
      (libsource (lib "eagle-import") (part "C-EUC1206K"))
    )
    (comp (ref "C24")
      (value "10µF")
      (footprint "eagle-import:C1206K")
      (libsource (lib "eagle-import") (part "C-EUC1206K"))
    )
    (comp (ref "C25")
      (value "22pF")
      (footprint "eagle-import:C0603")
      (libsource (lib "eagle-import") (part "C-EUC0603"))
    )
    (comp (ref "C26")
      (value "22pF")
      (footprint "eagle-import:C0603")
      (libsource (lib "eagle-import") (part "C-EUC0603"))
    )
    (comp (ref "C27")
      (value "100n")
      (footprint "eagle-import:C0603")
      (libsource (lib "eagle-import") (part "C-EUC0603"))
    )
    (comp (ref "C28")
      (value "10µF")
      (footprint "eagle-import:C1206K")
      (libsource (lib "eagle-import") (part "C-EUC1206K"))
    )
    (comp (ref "C29")
      (value "100n")
      (footprint "eagle-import:C0603")
      (libsource (lib "eagle-import") (part "C-EUC0603"))
    )
    (comp (ref "C30")
      (value "10µF")
      (footprint "eagle-import:C1206K")
      (libsource (lib "eagle-import") (part "C-EUC1206K"))
    )
    (comp (ref "C31")
      (value "100n")
      (footprint "eagle-import:C0603")
      (libsource (lib "eagle-import") (part "C-EUC0603"))
    )
    (comp (ref "C32")
      (value "47µF")
      (footprint "eagle-import:C1206K")
      (libsource (lib "eagle-import") (part "C-EUC1206K"))
    )
    (comp (ref "C33")
      (value "3.3nF")
      (footprint "eagle-import:C0603")
      (libsource (lib "eagle-import") (part "C-EUC0603"))
    )
    (comp (ref "C34")
      (value "56nF")
      (footprint "eagle-import:C0603")
      (libsource (lib "eagle-import") (part "C-EUC0603"))
    )
    (comp (ref "C35")
      (value "47µF")
      (footprint "eagle-import:153CLV-0605")
      (libsource (lib "eagle-import") (part "CPOL-EU153CLV-0605"))
    )
    (comp (ref "C36")
      (value "5.6nF")
      (footprint "eagle-import:C0603")
      (libsource (lib "eagle-import") (part "C-EUC0603"))
    )
    (comp (ref "C37")
      (value "47µF")
      (footprint "eagle-import:153CLV-0605")
      (libsource (lib "eagle-import") (part "CPOL-EU153CLV-0605"))
    )
    (comp (ref "C38")
      (value "5.6nF")
      (footprint "eagle-import:C0603")
      (libsource (lib "eagle-import") (part "C-EUC0603"))
    )
    (comp (ref "C39")
      (value "47µF")
      (footprint "eagle-import:153CLV-0605")
      (libsource (lib "eagle-import") (part "CPOL-EU153CLV-0605"))
    )
    (comp (ref "C40")
      (value "5.6nF")
      (footprint "eagle-import:C0603")
      (libsource (lib "eagle-import") (part "C-EUC0603"))
    )
    (comp (ref "C41")
      (value "47µF")
      (footprint "eagle-import:153CLV-0605")
      (libsource (lib "eagle-import") (part "CPOL-EU153CLV-0605"))
    )
    (comp (ref "C42")
      (value "5.6nF")
      (footprint "eagle-import:C0603")
      (libsource (lib "eagle-import") (part "C-EUC0603"))
    )
    (comp (ref "J6")
      (value "CONN_01")
      (footprint "eagle-import:1X01")
      (libsource (lib "eagle-import") (part "CONN_01"))
    )
    (comp (ref "Q1")
      (value "ZX5T953")
      (footprint "eagle-import:SOT223")
      (libsource (lib "eagle-import") (part "FZT753SMD"))
    )
    (comp (ref "Q2")
      (value "12.288MHz")
      (footprint "eagle-import:CSM-7X-DU")
      (libsource (lib "eagle-import") (part "CSM-7X-DU"))
    )
    (comp (ref "R15")
      (value "1kΩ")
      (footprint "eagle-import:R0603")
      (libsource (lib "eagle-import") (part "R-EU_R0603"))
    )
    (comp (ref "R16")
      (value "10kΩ")
      (footprint "eagle-import:R0603")
      (libsource (lib "eagle-import") (part "R-EU_R0603"))
    )
    (comp (ref "R17")
      (value "18kΩ")
      (footprint "eagle-import:R0603")
      (libsource (lib "eagle-import") (part "R-EU_R0603"))
    )
    (comp (ref "R18")
      (value "18kΩ")
      (footprint "eagle-import:R0603")
      (libsource (lib "eagle-import") (part "R-EU_R0603"))
    )
    (comp (ref "R19")
      (value "18kΩ")
      (footprint "eagle-import:R0603")
      (libsource (lib "eagle-import") (part "R-EU_R0603"))
    )
    (comp (ref "R20")
      (value "100Ω")
      (footprint "eagle-import:R0603")
      (libsource (lib "eagle-import") (part "R-EU_R0603"))
    )
    (comp (ref "R21")
      (value "475Ω")
      (footprint "eagle-import:R0603")
      (libsource (lib "eagle-import") (part "R-EU_R0603"))
    )
    (comp (ref "R22")
      (value "560Ω")
      (footprint "eagle-import:R0603")
      (libsource (lib "eagle-import") (part "R-EU_R0603"))
    )
    (comp (ref "R23")
      (value "560Ω")
      (footprint "eagle-import:R0603")
      (libsource (lib "eagle-import") (part "R-EU_R0603"))
    )
    (comp (ref "R24")
      (value "560Ω")
      (footprint "eagle-import:R0603")
      (libsource (lib "eagle-import") (part "R-EU_R0603"))
    )
    (comp (ref "R25")
      (value "560Ω")
      (footprint "eagle-import:R0603")
      (libsource (lib "eagle-import") (part "R-EU_R0603"))
    )
    (comp (ref "SJ1")
      (value "SJ2W")
      (footprint "eagle-import:SJ_2")
      (libsource (lib "eagle-import") (part "SJ2W"))
    )
    (comp (ref "SJ6") (value "SJ") (footprint "eagle-import:SJ") (libsource (lib "eagle-import") (part "SJ")))
    (comp (ref "SJ7") (value "SJ") (footprint "eagle-import:SJ") (libsource (lib "eagle-import") (part "SJ")))
    (comp (ref "SJ8") (value "SJ") (footprint "eagle-import:SJ") (libsource (lib "eagle-import") (part "SJ")))
    (comp (ref "SJ9") (value "SJ") (footprint "eagle-import:SJ") (libsource (lib "eagle-import") (part "SJ")))
    (comp (ref "U1")
      (value "ADAU1701JSTZ")
      (footprint "eagle-import:ST_48_ADI")
      (libsource (lib "eagle-import") (part "ADAU1701JSTZ"))
    )
    (comp (ref "C1")
      (value "10000µF")
      (footprint "eagle-import:EB35D")
      (libsource (lib "eagle-import") (part "CPOL-EUE10-35"))
    )
    (comp (ref "C2")
      (value "10µF")
      (footprint "eagle-import:153CLV-0605")
      (libsource (lib "eagle-import") (part "CPOL-EU153CLV-0605"))
    )
    (comp (ref "C3")
      (value "1.2nF")
      (footprint "eagle-import:C0603")
      (libsource (lib "eagle-import") (part "C-EUC0603"))
    )
    (comp (ref "C4")
      (value "6.8pF")
      (footprint "eagle-import:C0603")
      (libsource (lib "eagle-import") (part "C-EUC0603"))
    )
    (comp (ref "C5")
      (value "100nF")
      (footprint "eagle-import:C0603")
      (libsource (lib "eagle-import") (part "C-EUC0603"))
    )
    (comp (ref "C6")
      (value "47µF")
      (footprint "eagle-import:153CLV-0807")
      (libsource (lib "eagle-import") (part "CPOL-EU153CLV-0807"))
    )
    (comp (ref "C7")
      (value "100nF")
      (footprint "eagle-import:C0603")
      (libsource (lib "eagle-import") (part "C-EUC0603"))
    )
    (comp (ref "C8")
      (value "2.2nF")
      (footprint "eagle-import:C0603")
      (libsource (lib "eagle-import") (part "C-EUC0603"))
    )
    (comp (ref "C9")
      (value "100nF")
      (footprint "eagle-import:C0603")
      (libsource (lib "eagle-import") (part "C-EUC0603"))
    )
    (comp (ref "C10")
      (value "10µF")
      (footprint "eagle-import:153CLV-0605")
      (libsource (lib "eagle-import") (part "CPOL-EU153CLV-0605"))
    )
    (comp (ref "C11")
      (value "10µF")
      (footprint "eagle-import:153CLV-0605")
      (libsource (lib "eagle-import") (part "CPOL-EU153CLV-0605"))
    )
    (comp (ref "C12")
      (value "10µF")
      (footprint "eagle-import:C1206")
      (libsource (lib "eagle-import") (part "C-EUC1206"))
    )
    (comp (ref "C13")
      (value "10µF")
      (footprint "eagle-import:C1206")
      (libsource (lib "eagle-import") (part "C-EUC1206"))
    )
    (comp (ref "C14")
      (value "100nF")
      (footprint "eagle-import:C0603")
      (libsource (lib "eagle-import") (part "C-EUC0603"))
    )
    (comp (ref "D1")
      (value "STPS20M100SG-TR")
      (footprint "eagle-import:TO-263_D2PAK")
      (libsource (lib "eagle-import") (part "STPS20M100SG-TR"))
    )
    (comp (ref "IC1")
      (value "REG1117")
      (footprint "eagle-import:SOT223")
      (libsource (lib "eagle-import") (part "REG1117"))
    )
    (comp (ref "L1")
      (value "15µH")
      (footprint "eagle-import:INDUCTOR_SDR1307")
      (libsource (lib "eagle-import") (part "INDUCTOR-SDR13-27UH"))
    )
    (comp (ref "L2")
      (value "1µH")
      (footprint "eagle-import:INDUCTOR_4X4MM")
      (libsource (lib "eagle-import") (part "4.7μH_SHIELDED_INDUCTORNPIS_LS"))
    )
    (comp (ref "R1")
      (value "187kΩ")
      (footprint "eagle-import:R0603")
      (libsource (lib "eagle-import") (part "R-EU_R0603"))
    )
    (comp (ref "R2")
      (value "44.2kΩ")
      (footprint "eagle-import:R0603")
      (libsource (lib "eagle-import") (part "R-EU_R0603"))
    )
    (comp (ref "R3")
      (value "147kΩ")
      (footprint "eagle-import:R0603")
      (libsource (lib "eagle-import") (part "R-EU_R0603"))
    )
    (comp (ref "R4")
      (value "10.5kΩ")
      (footprint "eagle-import:R0603")
      (libsource (lib "eagle-import") (part "R-EU_R0603"))
    )
    (comp (ref "R5")
      (value "100kΩ")
      (footprint "eagle-import:R0603")
      (libsource (lib "eagle-import") (part "R-EU_R0603"))
    )
    (comp (ref "R6")
      (value "100kΩ")
      (footprint "eagle-import:R0603")
      (libsource (lib "eagle-import") (part "R-EU_R0603"))
    )
    (comp (ref "R7")
      (value "619kΩ")
      (footprint "eagle-import:R0603")
      (libsource (lib "eagle-import") (part "R-EU_R0603"))
    )
    (comp (ref "REG1")
      (value "TPS54560B-Q1")
      (footprint "eagle-import:HSOP8")
      (libsource (lib "eagle-import") (part "TPS54560B-Q1"))
    )
    (comp (ref "REG2")
      (value "TPS621351RGXR")
      (footprint "eagle-import:RGX0011A")
      (fields (field (name "MF") "Texas Instruments"))
      (libsource (lib "eagle-import") (part "TPS621351RGXR"))
    )
  )
  (nets
    (net (code "1") (name "+3V3") (class "Default")
      (node (ref "C13") (pin "1") (pinfunction "1_1") (pintype "passive"))
      (node (ref "C14") (pin "1") (pinfunction "1_1") (pintype "passive"))
      (node (ref "C15") (pin "2") (pinfunction "2_2") (pintype "passive"))
      (node (ref "C18") (pin "1") (pinfunction "1_1") (pintype "passive"))
      (node (ref "C19") (pin "1") (pinfunction "1_1") (pintype "passive"))
      (node (ref "C20") (pin "1") (pinfunction "1_1") (pintype "passive"))
      (node (ref "C21") (pin "1") (pinfunction "1_1") (pintype "passive"))
      (node (ref "C23") (pin "1") (pinfunction "1_1") (pintype "passive"))
      (node (ref "C24") (pin "1") (pinfunction "1_1") (pintype "passive"))
      (node (ref "C33") (pin "2") (pinfunction "2_2") (pintype "passive"))
      (node (ref "ESP") (pin "2") (pinfunction "3V3_2") (pintype "power_in"))
      (node (ref "IC1") (pin "2") (pinfunction "VOUT_2") (pintype "output"))
      (node (ref "PAD10") (pin "1") (pinfunction "P_1") (pintype "passive"))
      (node (ref "PAD2") (pin "1") (pinfunction "P_1") (pintype "passive"))
      (node (ref "PAD4") (pin "1") (pinfunction "P_1") (pintype "passive"))
      (node (ref "Q1") (pin "3") (pinfunction "E_3") (pintype "passive"))
      (node (ref "R10") (pin "E") (pinfunction "E_E") (pintype "passive"))
      (node (ref "R11") (pin "E") (pinfunction "E_E") (pintype "passive"))
      (node (ref "R12") (pin "E") (pinfunction "E_E") (pintype "passive"))
      (node (ref "R13") (pin "1") (pinfunction "1_1") (pintype "passive"))
      (node (ref "R14") (pin "1") (pinfunction "1_1") (pintype "passive"))
      (node (ref "R15") (pin "2") (pinfunction "2_2") (pintype "passive"))
      (node (ref "R16") (pin "2") (pinfunction "2_2") (pintype "passive"))
      (node (ref "R21") (pin "1") (pinfunction "1_1") (pintype "passive"))
      (node (ref "R31") (pin "2") (pinfunction "2_2") (pintype "passive"))
      (node (ref "R45") (pin "2") (pinfunction "2_2") (pintype "passive"))
      (node (ref "R8") (pin "2") (pinfunction "2_2") (pintype "passive"))
      (node (ref "R9") (pin "E") (pinfunction "E_E") (pintype "passive"))
      (node (ref "SJ1") (pin "3") (pinfunction "3_3") (pintype "passive"))
      (node (ref "U1") (pin "18") (pinfunction "IOVDD_18") (pintype "power_in"))
      (node (ref "U1") (pin "34") (pinfunction "PVDD_34") (pintype "power_in"))
      (node (ref "U1") (pin "36") (pinfunction "AVDD_2_36") (pintype "power_in"))
      (node (ref "U1") (pin "39") (pinfunction "PLL_MODE1_39") (pintype "input"))
      (node (ref "U1") (pin "48") (pinfunction "AVDD_48") (pintype "power_in"))
    )
    (net (code "2") (name "+5V") (class "Default")
      (node (ref "C11") (pin "+") (pinfunction "+_+") (pintype "passive"))
      (node (ref "J1") (pin "1") (pinfunction "VBUS_1") (pintype "bidirectional"))
      (node (ref "J2") (pin "1") (pinfunction "VBUS_1") (pintype "bidirectional"))
      (node (ref "L2") (pin "P$2") (pinfunction "2_P$2") (pintype "passive"))
      (node (ref "PAD5") (pin "1") (pinfunction "P_1") (pintype "passive"))
      (node (ref "PAD6") (pin "1") (pinfunction "P_1") (pintype "passive"))
      (node (ref "PAD7") (pin "1") (pinfunction "P_1") (pintype "passive"))
      (node (ref "R5") (pin "2") (pinfunction "2_2") (pintype "passive"))
      (node (ref "R7") (pin "2") (pinfunction "2_2") (pintype "passive"))
      (node (ref "REG2") (pin "6") (pinfunction "VOS_6") (pintype "input"))
    )
    (net (code "3") (name "+12V") (class "Default")
      (node (ref "C10") (pin "+") (pinfunction "+_+") (pintype "passive"))
      (node (ref "C12") (pin "1") (pinfunction "1_1") (pintype "passive"))
      (node (ref "C6") (pin "+") (pinfunction "+_+") (pintype "passive"))
      (node (ref "C9") (pin "1") (pinfunction "1_1") (pintype "passive"))
      (node (ref "IC1") (pin "3") (pinfunction "VIN_3") (pintype "input"))
      (node (ref "J7") (pin "2") (pinfunction "2_2") (pintype "passive"))
      (node (ref "L1") (pin "P$2") (pinfunction "2_P$2") (pintype "passive"))
      (node (ref "R3") (pin "2") (pinfunction "2_2") (pintype "passive"))
      (node (ref "REG2") (pin "1") (pinfunction "VIN_1") (pintype "power_in"))
      (node (ref "REG2") (pin "8") (pinfunction "EN_8") (pintype "input"))
      (node (ref "X1") (pin "1") (pinfunction "KL_1") (pintype "passive"))
    )
    (net (code "4") (name "AMP1_GAIN") (class "Default")
      (node (ref "JP1") (pin "2") (pinfunction "2_2") (pintype "passive"))
      (node (ref "JP2") (pin "2") (pinfunction "2_2") (pintype "passive"))
      (node (ref "JP3") (pin "2") (pinfunction "2_2") (pintype "passive"))
      (node (ref "JP4") (pin "2") (pinfunction "2_2") (pintype "passive"))
      (node (ref "U2") (pin "30") (pinfunction "GAIN_30") (pintype "passive"))
    )
    (net (code "5") (name "AMP1_IN_A") (class "Default")
      (node (ref "SJ2") (pin "2") (pinfunction "2_2") (pintype "passive"))
      (node (ref "U2") (pin "22") (pinfunction "INPA_22") (pintype "input"))
    )
    (net (code "6") (name "AMP1_IN_B") (class "Default")
      (node (ref "SJ3") (pin "2") (pinfunction "2_2") (pintype "passive"))
      (node (ref "U2") (pin "32") (pinfunction "INPB_32") (pintype "input"))
    )
    (net (code "7") (name "AMP1_MUTE") (class "Default")
      (node (ref "ESP") (pin "28") (pinfunction "IO17_28") (pintype "bidirectional"))
      (node (ref "R27") (pin "2") (pinfunction "2_2") (pintype "passive"))
      (node (ref "U2") (pin "21") (pinfunction "MUTE_21") (pintype "passive"))
    )
    (net (code "8") (name "AMP1_OUTA_N") (class "Default")
      (node (ref "C55") (pin "1") (pinfunction "1_1") (pintype "passive"))
      (node (ref "L4") (pin "P$1") (pinfunction "1_P$1") (pintype "passive"))
      (node (ref "U2") (pin "10") (pinfunction "OUTNA_2_10") (pintype "output"))
      (node (ref "U2") (pin "11") (pinfunction "OUTNA_11") (pintype "output"))
    )
    (net (code "9") (name "AMP1_OUTA_P") (class "Default")
      (node (ref "L3") (pin "P$1") (pinfunction "1_P$1") (pintype "passive"))
      (node (ref "R34") (pin "2") (pinfunction "2_2") (pintype "passive"))
      (node (ref "U2") (pin "16") (pinfunction "OUTPA_2_16") (pintype "output"))
      (node (ref "U2") (pin "17") (pinfunction "OUTPA_17") (pintype "output"))
    )
    (net (code "10") (name "AMP1_OUTB_N") (class "Default")
      (node (ref "C61") (pin "1") (pinfunction "1_1") (pintype "passive"))
      (node (ref "L6") (pin "P$1") (pinfunction "1_P$1") (pintype "passive"))
      (node (ref "U2") (pin "8") (pinfunction "OUTNB_2_8") (pintype "output"))
      (node (ref "U2") (pin "9") (pinfunction "OUTNB_9") (pintype "output"))
    )
    (net (code "11") (name "AMP1_PGND") (class "Default")
      (node (ref "C45") (pin "1") (pinfunction "1_1") (pintype "passive"))
      (node (ref "U2") (pin "18") (pinfunction "PGND_18") (pintype "passive"))
    )
    (net (code "12") (name "AMP1_ROSC") (class "Default")
      (node (ref "C48") (pin "2") (pinfunction "2_2") (pintype "passive"))
      (node (ref "R30") (pin "2") (pinfunction "2_2") (pintype "passive"))
      (node (ref "U2") (pin "24") (pinfunction "ROSC_24") (pintype "passive"))
    )
    (net (code "13") (name "AMP1_STANDBY") (class "Default")
      (node (ref "ESP") (pin "27") (pinfunction "IO16_27") (pintype "bidirectional"))
      (node (ref "R26") (pin "2") (pinfunction "2_2") (pintype "passive"))
      (node (ref "U2") (pin "20") (pinfunction "STBY_20") (pintype "passive"))
    )
    (net (code "14") (name "AMP1_SYNCLK") (class "Default")
      (node (ref "U2") (pin "25") (pinfunction "SYNCLK_25") (pintype "passive"))
    )
    (net (code "15") (name "AMP1_VDDPW") (class "Default")
      (node (ref "C45") (pin "2") (pinfunction "2_2") (pintype "passive"))
      (node (ref "R28") (pin "2") (pinfunction "2_2") (pintype "passive"))
      (node (ref "U2") (pin "19") (pinfunction "VDDPW_19") (pintype "power_in"))
    )
    (net (code "16") (name "AMP1_VDDS") (class "Default")
      (node (ref "C46") (pin "1") (pinfunction "1_1") (pintype "passive"))
      (node (ref "JP4") (pin "1") (pinfunction "1_1") (pintype "passive"))
      (node (ref "R28") (pin "1") (pinfunction "1_1") (pintype "passive"))
      (node (ref "R29") (pin "2") (pinfunction "2_2") (pintype "passive"))
      (node (ref "U2") (pin "26") (pinfunction "VDDS_26") (pintype "power_in"))
    )
    (net (code "17") (name "AMP1_VREF") (class "Default")
      (node (ref "C47") (pin "1") (pinfunction "1_1") (pintype "passive"))
      (node (ref "U2") (pin "34") (pinfunction "VREF_34") (pintype "power_in"))
    )
    (net (code "18") (name "AMP1_VSS") (class "Default")
      (node (ref "C43") (pin "1") (pinfunction "1_1") (pintype "passive"))
      (node (ref "U2") (pin "36") (pinfunction "VSS_36") (pintype "passive"))
    )
    (net (code "19") (name "AMP2_GAIN") (class "Default")
      (node (ref "JP5") (pin "2") (pinfunction "2_2") (pintype "passive"))
      (node (ref "JP6") (pin "2") (pinfunction "2_2") (pintype "passive"))
      (node (ref "JP7") (pin "2") (pinfunction "2_2") (pintype "passive"))
      (node (ref "JP8") (pin "2") (pinfunction "2_2") (pintype "passive"))
      (node (ref "U3") (pin "30") (pinfunction "GAIN_30") (pintype "passive"))
    )
    (net (code "20") (name "AMP2_IN_A") (class "Default")
      (node (ref "SJ5") (pin "2") (pinfunction "2_2") (pintype "passive"))
      (node (ref "U3") (pin "22") (pinfunction "INPA_22") (pintype "input"))
    )
    (net (code "21") (name "AMP2_IN_B") (class "Default")
      (node (ref "SJ4") (pin "2") (pinfunction "2_2") (pintype "passive"))
      (node (ref "U3") (pin "32") (pinfunction "INPB_32") (pintype "input"))
    )
    (net (code "22") (name "AMP2_MUTE") (class "Default")
      (node (ref "ESP") (pin "9") (pinfunction "IO33_9") (pintype "bidirectional"))
      (node (ref "R41") (pin "2") (pinfunction "2_2") (pintype "passive"))
      (node (ref "U3") (pin "21") (pinfunction "MUTE_21") (pintype "passive"))
    )
    (net (code "23") (name "AMP2_OUTA_N") (class "Default")
      (node (ref "C79") (pin "1") (pinfunction "1_1") (pintype "passive"))
      (node (ref "L8") (pin "P$1") (pinfunction "1_P$1") (pintype "passive"))
      (node (ref "U3") (pin "10") (pinfunction "OUTNA_2_10") (pintype "output"))
      (node (ref "U3") (pin "11") (pinfunction "OUTNA_11") (pintype "output"))
    )
    (net (code "24") (name "AMP2_OUTA_P") (class "Default")
      (node (ref "L7") (pin "P$1") (pinfunction "1_P$1") (pintype "passive"))
      (node (ref "R48") (pin "2") (pinfunction "2_2") (pintype "passive"))
      (node (ref "U3") (pin "16") (pinfunction "OUTPA_2_16") (pintype "output"))
      (node (ref "U3") (pin "17") (pinfunction "OUTPA_17") (pintype "output"))
    )
    (net (code "25") (name "AMP2_OUTB_N") (class "Default")
      (node (ref "C85") (pin "1") (pinfunction "1_1") (pintype "passive"))
      (node (ref "L10") (pin "P$1") (pinfunction "1_P$1") (pintype "passive"))
      (node (ref "U3") (pin "8") (pinfunction "OUTNB_2_8") (pintype "output"))
      (node (ref "U3") (pin "9") (pinfunction "OUTNB_9") (pintype "output"))
    )
    (net (code "26") (name "AMP2_OUTB_P") (class "Default")
      (node (ref "L9") (pin "P$1") (pinfunction "1_P$1") (pintype "passive"))
      (node (ref "R51") (pin "2") (pinfunction "2_2") (pintype "passive"))
      (node (ref "U3") (pin "2") (pinfunction "OUTPB_2_2") (pintype "output"))
      (node (ref "U3") (pin "3") (pinfunction "OUTPB_3") (pintype "output"))
    )
    (net (code "27") (name "AMP2_PGND") (class "Default")
      (node (ref "C69") (pin "1") (pinfunction "1_1") (pintype "passive"))
      (node (ref "U3") (pin "18") (pinfunction "PGND_18") (pintype "passive"))
    )
    (net (code "28") (name "AMP2_ROSC") (class "Default")
      (node (ref "C72") (pin "2") (pinfunction "2_2") (pintype "passive"))
      (node (ref "R44") (pin "2") (pinfunction "2_2") (pintype "passive"))
      (node (ref "U3") (pin "24") (pinfunction "ROSC_24") (pintype "passive"))
    )
    (net (code "29") (name "AMP2_STANDBY") (class "Default")
      (node (ref "ESP") (pin "8") (pinfunction "IO32_8") (pintype "bidirectional"))
      (node (ref "R40") (pin "2") (pinfunction "2_2") (pintype "passive"))
      (node (ref "U3") (pin "20") (pinfunction "STBY_20") (pintype "passive"))
    )
    (net (code "30") (name "AMP2_SYNCLK") (class "Default")
      (node (ref "U3") (pin "25") (pinfunction "SYNCLK_25") (pintype "passive"))
    )
    (net (code "31") (name "AMP2_VDDPW") (class "Default")
      (node (ref "C69") (pin "2") (pinfunction "2_2") (pintype "passive"))
      (node (ref "R42") (pin "2") (pinfunction "2_2") (pintype "passive"))
      (node (ref "U3") (pin "19") (pinfunction "VDDPW_19") (pintype "power_in"))
    )
    (net (code "32") (name "AMP2_VDDS") (class "Default")
      (node (ref "C70") (pin "1") (pinfunction "1_1") (pintype "passive"))
      (node (ref "JP8") (pin "1") (pinfunction "1_1") (pintype "passive"))
      (node (ref "R42") (pin "1") (pinfunction "1_1") (pintype "passive"))
      (node (ref "R43") (pin "2") (pinfunction "2_2") (pintype "passive"))
      (node (ref "U3") (pin "26") (pinfunction "VDDS_26") (pintype "power_in"))
    )
    (net (code "33") (name "AMP2_VREF") (class "Default")
      (node (ref "C71") (pin "1") (pinfunction "1_1") (pintype "passive"))
      (node (ref "U3") (pin "34") (pinfunction "VREF_34") (pintype "power_in"))
    )
    (net (code "34") (name "AMP2_VSS") (class "Default")
      (node (ref "C67") (pin "1") (pinfunction "1_1") (pintype "passive"))
      (node (ref "U3") (pin "36") (pinfunction "VSS_36") (pintype "passive"))
    )
    (net (code "35") (name "AMP3_OUTB_P") (class "Default")
      (node (ref "L5") (pin "P$1") (pinfunction "1_P$1") (pintype "passive"))
      (node (ref "R37") (pin "2") (pinfunction "2_2") (pintype "passive"))
      (node (ref "U2") (pin "2") (pinfunction "OUTPB_2_2") (pintype "output"))
      (node (ref "U2") (pin "3") (pinfunction "OUTPB_3") (pintype "output"))
    )
    (net (code "36") (name "A_LINE_A") (class "Default")
      (node (ref "C36") (pin "1") (pinfunction "1_1") (pintype "passive"))
      (node (ref "R22") (pin "1") (pinfunction "1_1") (pintype "passive"))
      (node (ref "SJ3") (pin "1") (pinfunction "1_1") (pintype "passive"))
      (node (ref "SJ6") (pin "2") (pinfunction "2_2") (pintype "passive"))
    )
    (net (code "37") (name "A_LINE_B") (class "Default")
      (node (ref "C38") (pin "1") (pinfunction "1_1") (pintype "passive"))
      (node (ref "R23") (pin "1") (pinfunction "1_1") (pintype "passive"))
      (node (ref "SJ2") (pin "1") (pinfunction "1_1") (pintype "passive"))
      (node (ref "SJ7") (pin "2") (pinfunction "2_2") (pintype "passive"))
    )
    (net (code "38") (name "A_LINE_C") (class "Default")
      (node (ref "C40") (pin "1") (pinfunction "1_1") (pintype "passive"))
      (node (ref "R24") (pin "1") (pinfunction "1_1") (pintype "passive"))
      (node (ref "SJ4") (pin "1") (pinfunction "1_1") (pintype "passive"))
      (node (ref "SJ8") (pin "2") (pinfunction "2_2") (pintype "passive"))
    )
    (net (code "39") (name "A_LINE_D") (class "Default")
      (node (ref "C42") (pin "1") (pinfunction "1_1") (pintype "passive"))
      (node (ref "R25") (pin "1") (pinfunction "1_1") (pintype "passive"))
      (node (ref "SJ5") (pin "1") (pinfunction "1_1") (pintype "passive"))
      (node (ref "SJ9") (pin "2") (pinfunction "2_2") (pintype "passive"))
    )
    (net (code "40") (name "DSP_DVDD") (class "Default")
      (node (ref "C16") (pin "1") (pinfunction "1_1") (pintype "passive"))
      (node (ref "C17") (pin "1") (pinfunction "1_1") (pintype "passive"))
      (node (ref "C22") (pin "1") (pinfunction "1_1") (pintype "passive"))
      (node (ref "Q1") (pin "2") (pinfunction "C_2") (pintype "passive"))
      (node (ref "Q1") (pin "4") (pinfunction "C_4") (pintype "passive"))
      (node (ref "U1") (pin "13") (pinfunction "DVDD_2_13") (pintype "power_in"))
      (node (ref "U1") (pin "24") (pinfunction "DVDD_24") (pintype "power_in"))
    )
    (net (code "41") (name "DSP_IN_BCLK") (class "Default")
      (node (ref "ESP") (pin "12") (pinfunction "IO27_12") (pintype "bidirectional"))
      (node (ref "U1") (pin "9") (pinfunction "MP5_9") (pintype "bidirectional"))
    )
    (net (code "42") (name "DSP_IN_LRCLK") (class "Default")
      (node (ref "ESP") (pin "16") (pinfunction "IO13_16") (pintype "bidirectional"))
      (node (ref "U1") (pin "8") (pinfunction "MP4_8") (pintype "bidirectional"))
    )
    (net (code "43") (name "DSP_IN_SDATA0") (class "Default")
      (node (ref "ESP") (pin "11") (pinfunction "IO26_11") (pintype "bidirectional"))
      (node (ref "U1") (pin "10") (pinfunction "MP1_10") (pintype "bidirectional"))
    )
    (net (code "44") (name "DSP_IN_SDATA1") (class "Default")
      (node (ref "U1") (pin "11") (pinfunction "MP0_11") (pintype "bidirectional"))
    )
    (net (code "45") (name "DSP_MCLKI") (class "Default")
      (node (ref "C26") (pin "1") (pinfunction "1_1") (pintype "passive"))
      (node (ref "Q2") (pin "1") (pinfunction "1_1") (pintype "passive"))
      (node (ref "U1") (pin "32") (pinfunction "MCLKI_32") (pintype "input"))
    )
    (net (code "46") (name "DSP_OSCO") (class "Default")
      (node (ref "R20") (pin "1") (pinfunction "1_1") (pintype "passive"))
      (node (ref "U1") (pin "31") (pinfunction "OSCO_31") (pintype "output"))
    )
    (net (code "47") (name "DSP_OUT_BCLK") (class "Default")
      (node (ref "U1") (pin "19") (pinfunction "MP11_19") (pintype "bidirectional"))
    )
    (net (code "48") (name "DSP_OUT_LRCLK") (class "Default")
      (node (ref "U1") (pin "16") (pinfunction "MP10_16") (pintype "bidirectional"))
    )
    (net (code "49") (name "DSP_OUT_SDATA0") (class "Default")
      (node (ref "U1") (pin "15") (pinfunction "MP6_15") (pintype "bidirectional"))
    )
    (net (code "50") (name "DSP_OUT_SDATA1") (class "Default")
      (node (ref "U1") (pin "14") (pinfunction "MP7_14") (pintype "bidirectional"))
    )
    (net (code "51") (name "DSP_RESET") (class "Default")
      (node (ref "ESP") (pin "14") (pinfunction "IO12_14") (pintype "bidirectional"))
      (node (ref "J6") (pin "1") (pinfunction "1_1") (pintype "passive"))
      (node (ref "R16") (pin "1") (pinfunction "1_1") (pintype "passive"))
      (node (ref "U1") (pin "5") (pinfunction "~{RESET}_5") (pintype "input"))
    )
    (net (code "52") (name "DSP_SELFBOOT") (class "Default")
      (node (ref "SJ1") (pin "2") (pinfunction "2_2") (pintype "passive"))
      (node (ref "U1") (pin "6") (pinfunction "SELFBOOT_6") (pintype "input"))
    )
    (net (code "53") (name "DSP_VDRIVE") (class "Default")
      (node (ref "Q1") (pin "1") (pinfunction "B_1") (pintype "passive"))
      (node (ref "R15") (pin "1") (pinfunction "1_1") (pintype "passive"))
      (node (ref "U1") (pin "17") (pinfunction "VDRIVE_17") (pintype "output"))
    )
    (net (code "54") (name "DSP_VOUT0") (class "Default")
      (node (ref "C35") (pin "+") (pinfunction "+_+") (pintype "passive"))
      (node (ref "SJ6") (pin "1") (pinfunction "1_1") (pintype "passive"))
      (node (ref "U1") (pin "46") (pinfunction "VOUT0_46") (pintype "output"))
    )
    (net (code "55") (name "DSP_VOUT1") (class "Default")
      (node (ref "C37") (pin "+") (pinfunction "+_+") (pintype "passive"))
      (node (ref "SJ7") (pin "1") (pinfunction "1_1") (pintype "passive"))
      (node (ref "U1") (pin "45") (pinfunction "VOUT1_45") (pintype "output"))
    )
    (net (code "56") (name "DSP_VOUT2") (class "Default")
      (node (ref "C39") (pin "+") (pinfunction "+_+") (pintype "passive"))
      (node (ref "SJ8") (pin "1") (pinfunction "1_1") (pintype "passive"))
      (node (ref "U1") (pin "44") (pinfunction "VOUT2_44") (pintype "output"))
    )
    (net (code "57") (name "DSP_VOUT3") (class "Default")
      (node (ref "C41") (pin "+") (pinfunction "+_+") (pintype "passive"))
      (node (ref "SJ9") (pin "1") (pinfunction "1_1") (pintype "passive"))
      (node (ref "U1") (pin "43") (pinfunction "VOUT3_43") (pintype "output"))
    )
    (net (code "58") (name "ESP_CLK") (class "Default")
      (node (ref "ESP") (pin "20") (pinfunction "CLK_20") (pintype "bidirectional"))
    )
    (net (code "59") (name "ESP_CMD") (class "Default")
      (node (ref "ESP") (pin "19") (pinfunction "CMD_19") (pintype "bidirectional"))
    )
    (net (code "60") (name "ESP_EN") (class "Default")
      (node (ref "ESP") (pin "3") (pinfunction "EN_3") (pintype "input"))
      (node (ref "R8") (pin "1") (pinfunction "1_1") (pintype "passive"))
      (node (ref "S1") (pin "B2") (pinfunction "2_B2") (pintype "passive"))
    )
    (net (code "61") (name "ESP_IO0") (class "Default")
      (node (ref "ESP") (pin "25") (pinfunction "IO0_25") (pintype "bidirectional"))
      (node (ref "S2") (pin "A2") (pinfunction "1_A2") (pintype "passive"))
    )
    (net (code "62") (name "ESP_IO2") (class "Default")
      (node (ref "ESP") (pin "24") (pinfunction "IO2_24") (pintype "bidirectional"))
    )
    (net (code "63") (name "ESP_IO4") (class "Default")
      (node (ref "ESP") (pin "26") (pinfunction "IO4_26") (pintype "bidirectional"))
      (node (ref "IO4") (pin "1") (pinfunction "P_1") (pintype "passive"))
    )
    (net (code "64") (name "ESP_IO5") (class "Default")
      (node (ref "ESP") (pin "29") (pinfunction "IO5_29") (pintype "bidirectional"))
      (node (ref "IO5") (pin "1") (pinfunction "P_1") (pintype "passive"))
    )
    (net (code "65") (name "ESP_IO14") (class "Default")
      (node (ref "ESP") (pin "13") (pinfunction "IO14_13") (pintype "bidirectional"))
      (node (ref "IO14") (pin "1") (pinfunction "P_1") (pintype "passive"))
    )
    (net (code "66") (name "ESP_IO15") (class "Default")
      (node (ref "ESP") (pin "23") (pinfunction "IO15_23") (pintype "bidirectional"))
    )
    (net (code "67") (name "ESP_IO18") (class "Default")
      (node (ref "ESP") (pin "30") (pinfunction "IO18_30") (pintype "bidirectional"))
      (node (ref "IO18") (pin "1") (pinfunction "P_1") (pintype "passive"))
    )
    (net (code "68") (name "ESP_IO19") (class "Default")
      (node (ref "ESP") (pin "31") (pinfunction "IO19_31") (pintype "bidirectional"))
      (node (ref "IO19") (pin "1") (pinfunction "P_1") (pintype "passive"))
    )
    (net (code "69") (name "ESP_IO23") (class "Default")
      (node (ref "ESP") (pin "37") (pinfunction "IO23_37") (pintype "bidirectional"))
      (node (ref "IO23") (pin "1") (pinfunction "P_1") (pintype "passive"))
    )
    (net (code "70") (name "ESP_IO25") (class "Default")
      (node (ref "ESP") (pin "10") (pinfunction "IO25_10") (pintype "bidirectional"))
      (node (ref "IO25") (pin "1") (pinfunction "P_1") (pintype "passive"))
    )
    (net (code "71") (name "ESP_IO34") (class "Default")
      (node (ref "ESP") (pin "6") (pinfunction "IO34_6") (pintype "bidirectional"))
      (node (ref "IO34") (pin "1") (pinfunction "P_1") (pintype "passive"))
    )
    (net (code "72") (name "ESP_IO35") (class "Default")
      (node (ref "ESP") (pin "7") (pinfunction "IO35_7") (pintype "bidirectional"))
      (node (ref "IO35") (pin "1") (pinfunction "P_1") (pintype "passive"))
    )
    (net (code "73") (name "ESP_RXD0") (class "Default")
      (node (ref "ESP") (pin "34") (pinfunction "RXD0_34") (pintype "bidirectional"))
      (node (ref "J3") (pin "2") (pinfunction "2_2") (pintype "passive"))
    )
    (net (code "74") (name "ESP_SD0") (class "Default")
      (node (ref "ESP") (pin "21") (pinfunction "SD0_21") (pintype "bidirectional"))
    )
    (net (code "75") (name "ESP_SD1") (class "Default")
      (node (ref "ESP") (pin "22") (pinfunction "SD1_22") (pintype "bidirectional"))
    )
    (net (code "76") (name "ESP_SD2") (class "Default")
      (node (ref "ESP") (pin "17") (pinfunction "SD2_17") (pintype "bidirectional"))
    )
    (net (code "77") (name "ESP_SD3") (class "Default")
      (node (ref "ESP") (pin "18") (pinfunction "SD3_18") (pintype "bidirectional"))
    )
    (net (code "78") (name "ESP_SENSOR_VN") (class "Default")
      (node (ref "ESP") (pin "5") (pinfunction "SENSOR_VN_5") (pintype "bidirectional"))
    )
    (net (code "79") (name "ESP_SENSOR_VP") (class "Default")
      (node (ref "ESP") (pin "4") (pinfunction "SENSOR_VP_4") (pintype "bidirectional"))
    )
    (net (code "80") (name "ESP_TXD0") (class "Default")
      (node (ref "ESP") (pin "35") (pinfunction "TXD0_35") (pintype "bidirectional"))
      (node (ref "J3") (pin "1") (pinfunction "1_1") (pintype "passive"))
    )
    (net (code "81") (name "GND") (class "Default")
      (node (ref "C1") (pin "-") (pinfunction "-_-") (pintype "passive"))
      (node (ref "C10") (pin "-") (pinfunction "-_-") (pintype "passive"))
      (node (ref "C11") (pin "-") (pinfunction "-_-") (pintype "passive"))
      (node (ref "C12") (pin "2") (pinfunction "2_2") (pintype "passive"))
      (node (ref "C13") (pin "2") (pinfunction "2_2") (pintype "passive"))
      (node (ref "C14") (pin "2") (pinfunction "2_2") (pintype "passive"))
      (node (ref "C15") (pin "1") (pinfunction "1_1") (pintype "passive"))
      (node (ref "C16") (pin "2") (pinfunction "2_2") (pintype "passive"))
      (node (ref "C17") (pin "2") (pinfunction "2_2") (pintype "passive"))
      (node (ref "C18") (pin "2") (pinfunction "2_2") (pintype "passive"))
      (node (ref "C19") (pin "2") (pinfunction "2_2") (pintype "passive"))
      (node (ref "C2") (pin "-") (pinfunction "-_-") (pintype "passive"))
      (node (ref "C20") (pin "2") (pinfunction "2_2") (pintype "passive"))
      (node (ref "C21") (pin "2") (pinfunction "2_2") (pintype "passive"))
      (node (ref "C22") (pin "2") (pinfunction "2_2") (pintype "passive"))
      (node (ref "C23") (pin "2") (pinfunction "2_2") (pintype "passive"))
      (node (ref "C24") (pin "2") (pinfunction "2_2") (pintype "passive"))
      (node (ref "C25") (pin "2") (pinfunction "2_2") (pintype "passive"))
      (node (ref "C26") (pin "2") (pinfunction "2_2") (pintype "passive"))
      (node (ref "C27") (pin "1") (pinfunction "1_1") (pintype "passive"))
      (node (ref "C28") (pin "1") (pinfunction "1_1") (pintype "passive"))
      (node (ref "C29") (pin "1") (pinfunction "1_1") (pintype "passive"))
      (node (ref "C3") (pin "2") (pinfunction "2_2") (pintype "passive"))
      (node (ref "C30") (pin "1") (pinfunction "1_1") (pintype "passive"))
      (node (ref "C31") (pin "1") (pinfunction "1_1") (pintype "passive"))
      (node (ref "C32") (pin "1") (pinfunction "1_1") (pintype "passive"))
      (node (ref "C36") (pin "2") (pinfunction "2_2") (pintype "passive"))
      (node (ref "C38") (pin "2") (pinfunction "2_2") (pintype "passive"))
      (node (ref "C4") (pin "2") (pinfunction "2_2") (pintype "passive"))
      (node (ref "C40") (pin "2") (pinfunction "2_2") (pintype "passive"))
      (node (ref "C42") (pin "2") (pinfunction "2_2") (pintype "passive"))
      (node (ref "C44") (pin "2") (pinfunction "2_2") (pintype "passive"))
      (node (ref "C46") (pin "2") (pinfunction "2_2") (pintype "passive"))
      (node (ref "C47") (pin "2") (pinfunction "2_2") (pintype "passive"))
      (node (ref "C48") (pin "1") (pinfunction "1_1") (pintype "passive"))
      (node (ref "C49") (pin "-") (pinfunction "-_-") (pintype "passive"))
      (node (ref "C50") (pin "-") (pinfunction "-_-") (pintype "passive"))
      (node (ref "C51") (pin "2") (pinfunction "2_2") (pintype "passive"))
      (node (ref "C52") (pin "2") (pinfunction "2_2") (pintype "passive"))
      (node (ref "C53") (pin "2") (pinfunction "2_2") (pintype "passive"))
      (node (ref "C54") (pin "2") (pinfunction "2_2") (pintype "passive"))
      (node (ref "C56") (pin "1") (pinfunction "1_1") (pintype "passive"))
      (node (ref "C57") (pin "2") (pinfunction "2_2") (pintype "passive"))
      (node (ref "C58") (pin "2") (pinfunction "2_2") (pintype "passive"))
      (node (ref "C59") (pin "2") (pinfunction "2_2") (pintype "passive"))
      (node (ref "C6") (pin "-") (pinfunction "-_-") (pintype "passive"))
      (node (ref "C63") (pin "1") (pinfunction "1_1") (pintype "passive"))
      (node (ref "C64") (pin "2") (pinfunction "2_2") (pintype "passive"))
      (node (ref "C65") (pin "2") (pinfunction "2_2") (pintype "passive"))
      (node (ref "C66") (pin "2") (pinfunction "2_2") (pintype "passive"))
      (node (ref "C68") (pin "2") (pinfunction "2_2") (pintype "passive"))
      (node (ref "C7") (pin "2") (pinfunction "2_2") (pintype "passive"))
      (node (ref "C70") (pin "2") (pinfunction "2_2") (pintype "passive"))
      (node (ref "C71") (pin "2") (pinfunction "2_2") (pintype "passive"))
      (node (ref "C72") (pin "1") (pinfunction "1_1") (pintype "passive"))
      (node (ref "C73") (pin "-") (pinfunction "-_-") (pintype "passive"))
      (node (ref "C74") (pin "-") (pinfunction "-_-") (pintype "passive"))
      (node (ref "C75") (pin "2") (pinfunction "2_2") (pintype "passive"))
      (node (ref "C76") (pin "2") (pinfunction "2_2") (pintype "passive"))
      (node (ref "C77") (pin "2") (pinfunction "2_2") (pintype "passive"))
      (node (ref "C78") (pin "2") (pinfunction "2_2") (pintype "passive"))
      (node (ref "C8") (pin "1") (pinfunction "1_1") (pintype "passive"))
      (node (ref "C80") (pin "1") (pinfunction "1_1") (pintype "passive"))
      (node (ref "C81") (pin "2") (pinfunction "2_2") (pintype "passive"))
      (node (ref "C82") (pin "2") (pinfunction "2_2") (pintype "passive"))
      (node (ref "C83") (pin "2") (pinfunction "2_2") (pintype "passive"))
      (node (ref "C87") (pin "1") (pinfunction "1_1") (pintype "passive"))
      (node (ref "C88") (pin "2") (pinfunction "2_2") (pintype "passive"))
      (node (ref "C89") (pin "2") (pinfunction "2_2") (pintype "passive"))
      (node (ref "C9") (pin "2") (pinfunction "2_2") (pintype "passive"))
      (node (ref "C90") (pin "2") (pinfunction "2_2") (pintype "passive"))
      (node (ref "D1") (pin "1") (pinfunction "A_1") (pintype "passive"))
      (node (ref "D1") (pin "3") (pinfunction "A_3") (pintype "passive"))
      (node (ref "ESP") (pin "1") (pinfunction "GND_1") (pintype "power_in"))
      (node (ref "ESP") (pin "15") (pinfunction "GND_15") (pintype "power_in"))
      (node (ref "ESP") (pin "38") (pinfunction "GND_38") (pintype "power_in"))
      (node (ref "ESP") (pin "GND") (pinfunction "GND_GND") (pintype "power_in"))
      (node (ref "GND") (pin "1") (pinfunction "P_1") (pintype "passive"))
      (node (ref "IC1") (pin "1") (pinfunction "GND_1") (pintype "power_in"))
      (node (ref "J1") (pin "4") (pinfunction "GND_4") (pintype "bidirectional"))
      (node (ref "J1") (pin "S1") (pinfunction "SHIELD_S1") (pintype "bidirectional"))
      (node (ref "J1") (pin "S2") (pinfunction "SHIELD_S2") (pintype "bidirectional"))
      (node (ref "J1") (pin "S3") (pinfunction "SHIELD_S3") (pintype "bidirectional"))
      (node (ref "J1") (pin "S4") (pinfunction "SHIELD_S4") (pintype "bidirectional"))
      (node (ref "J2") (pin "4") (pinfunction "GND_4") (pintype "bidirectional"))
      (node (ref "J2") (pin "S1") (pinfunction "SHIELD_S1") (pintype "bidirectional"))
      (node (ref "J2") (pin "S2") (pinfunction "SHIELD_S2") (pintype "bidirectional"))
      (node (ref "J2") (pin "S3") (pinfunction "SHIELD_S3") (pintype "bidirectional"))
      (node (ref "J2") (pin "S4") (pinfunction "SHIELD_S4") (pintype "bidirectional"))
      (node (ref "J3") (pin "3") (pinfunction "3_3") (pintype "passive"))
      (node (ref "J4") (pin "3") (pinfunction "3_3") (pintype "passive"))
      (node (ref "J5") (pin "1") (pinfunction "1_1") (pintype "passive"))
      (node (ref "J7") (pin "1") (pinfunction "1_1") (pintype "passive"))
      (node (ref "JP3") (pin "1") (pinfunction "1_1") (pintype "passive"))
      (node (ref "JP7") (pin "1") (pinfunction "1_1") (pintype "passive"))
      (node (ref "PAD1") (pin "1") (pinfunction "P_1") (pintype "passive"))
      (node (ref "PAD11") (pin "1") (pinfunction "P_1") (pintype "passive"))
      (node (ref "PAD12") (pin "1") (pinfunction "P_1") (pintype "passive"))
      (node (ref "PAD3") (pin "1") (pinfunction "P_1") (pintype "passive"))
      (node (ref "PAD8") (pin "1") (pinfunction "P_1") (pintype "passive"))
      (node (ref "PAD9") (pin "1") (pinfunction "P_1") (pintype "passive"))
      (node (ref "R1") (pin "1") (pinfunction "1_1") (pintype "passive"))
      (node (ref "R10") (pin "A") (pinfunction "A_A") (pintype "passive"))
      (node (ref "R11") (pin "A") (pinfunction "A_A") (pintype "passive"))
      (node (ref "R12") (pin "A") (pinfunction "A_A") (pintype "passive"))
      (node (ref "R18") (pin "2") (pinfunction "2_2") (pintype "passive"))
      (node (ref "R26") (pin "1") (pinfunction "1_1") (pintype "passive"))
      (node (ref "R27") (pin "1") (pinfunction "1_1") (pintype "passive"))
      (node (ref "R30") (pin "1") (pinfunction "1_1") (pintype "passive"))
      (node (ref "R33") (pin "1") (pinfunction "1_1") (pintype "passive"))
      (node (ref "R4") (pin "1") (pinfunction "1_1") (pintype "passive"))
      (node (ref "R40") (pin "1") (pinfunction "1_1") (pintype "passive"))
      (node (ref "R41") (pin "1") (pinfunction "1_1") (pintype "passive"))
      (node (ref "R44") (pin "1") (pinfunction "1_1") (pintype "passive"))
      (node (ref "R47") (pin "1") (pinfunction "1_1") (pintype "passive"))
      (node (ref "R6") (pin "1") (pinfunction "1_1") (pintype "passive"))
      (node (ref "R9") (pin "A") (pinfunction "A_A") (pintype "passive"))
      (node (ref "REG1") (pin "7") (pinfunction "GND_7") (pintype "bidirectional"))
      (node (ref "REG1") (pin "EXP") (pinfunction "PWRPD_EXP") (pintype "bidirectional"))
      (node (ref "REG2") (pin "10") (pinfunction "MODE_10") (pintype "input"))
      (node (ref "REG2") (pin "11") (pinfunction "VSEL_11") (pintype "input"))
      (node (ref "REG2") (pin "3") (pinfunction "GND_3") (pintype "power_in"))
      (node (ref "REG2") (pin "4") (pinfunction "FB2_4") (pintype "open_collector"))
      (node (ref "S1") (pin "A2") (pinfunction "1_A2") (pintype "passive"))
      (node (ref "S2") (pin "B2") (pinfunction "2_B2") (pintype "passive"))
      (node (ref "SJ1") (pin "1") (pinfunction "1_1") (pintype "passive"))
      (node (ref "U$1") (pin "-") (pinfunction "GND_-") (pintype "bidirectional"))
      (node (ref "U1") (pin "1") (pinfunction "AGND_2_1") (pintype "power_in"))
      (node (ref "U1") (pin "12") (pinfunction "DGND_2_12") (pintype "power_in"))
      (node (ref "U1") (pin "20") (pinfunction "ADDR1/CDATA/WB_20") (pintype "input"))
      (node (ref "U1") (pin "25") (pinfunction "DGND_25") (pintype "power_in"))
      (node (ref "U1") (pin "30") (pinfunction "RSVD_30") (pintype "passive"))
      (node (ref "U1") (pin "33") (pinfunction "PGND_33") (pintype "power_in"))
      (node (ref "U1") (pin "37") (pinfunction "AGND_3_37") (pintype "power_in"))
      (node (ref "U1") (pin "38") (pinfunction "PLL_MODE0_38") (pintype "input"))
      (node (ref "U1") (pin "42") (pinfunction "AGND_42") (pintype "power_in"))
      (node (ref "U1") (pin "7") (pinfunction "ADDR0_7") (pintype "input"))
      (node (ref "U2") (pin "1") (pinfunction "SUB_GND_1") (pintype "passive"))
      (node (ref "U2") (pin "14") (pinfunction "PGNDA_2_14") (pintype "passive"))
      (node (ref "U2") (pin "15") (pinfunction "PGNDA_15") (pintype "passive"))
      (node (ref "U2") (pin "23") (pinfunction "INNA_23") (pintype "input"))
      (node (ref "U2") (pin "27") (pinfunction "SGND_27") (pintype "passive"))
      (node (ref "U2") (pin "31") (pinfunction "MODE_31") (pintype "passive"))
      (node (ref "U2") (pin "33") (pinfunction "INNB_33") (pintype "input"))
      (node (ref "U2") (pin "4") (pinfunction "PGNDB_2_4") (pintype "passive"))
      (node (ref "U2") (pin "5") (pinfunction "PGNDB_5") (pintype "passive"))
      (node (ref "U2") (pin "EPAD") (pinfunction "EPAD_EPAD") (pintype "passive"))
      (node (ref "U3") (pin "1") (pinfunction "SUB_GND_1") (pintype "passive"))
      (node (ref "U3") (pin "14") (pinfunction "PGNDA_2_14") (pintype "passive"))
      (node (ref "U3") (pin "15") (pinfunction "PGNDA_15") (pintype "passive"))
      (node (ref "U3") (pin "23") (pinfunction "INNA_23") (pintype "input"))
      (node (ref "U3") (pin "27") (pinfunction "SGND_27") (pintype "passive"))
      (node (ref "U3") (pin "31") (pinfunction "MODE_31") (pintype "passive"))
      (node (ref "U3") (pin "33") (pinfunction "INNB_33") (pintype "input"))
      (node (ref "U3") (pin "4") (pinfunction "PGNDB_2_4") (pintype "passive"))
      (node (ref "U3") (pin "5") (pinfunction "PGNDB_5") (pintype "passive"))
      (node (ref "U3") (pin "EPAD") (pinfunction "EPAD_EPAD") (pintype "passive"))
      (node (ref "X1") (pin "2") (pinfunction "KL_2") (pintype "passive"))
    )
    (net (code "82") (name "I2C_SCL") (class "Default")
      (node (ref "ESP") (pin "36") (pinfunction "IO22_36") (pintype "bidirectional"))
      (node (ref "J4") (pin "1") (pinfunction "1_1") (pintype "passive"))
      (node (ref "R13") (pin "2") (pinfunction "2_2") (pintype "passive"))
      (node (ref "U1") (pin "23") (pinfunction "SCL/CCLK_23") (pintype "bidirectional"))
    )
    (net (code "83") (name "I2C_SDA") (class "Default")
      (node (ref "ESP") (pin "33") (pinfunction "IO21_33") (pintype "bidirectional"))
      (node (ref "J4") (pin "2") (pinfunction "2_2") (pintype "passive"))
      (node (ref "R14") (pin "2") (pinfunction "2_2") (pintype "passive"))
      (node (ref "U1") (pin "22") (pinfunction "SDA/COUT_22") (pintype "bidirectional"))
    )
    (net (code "84") (name "LINEIN_SW_L") (class "Default")
      (node (ref "J5") (pin "2") (pinfunction "2_2") (pintype "passive"))
      (node (ref "R19") (pin "2") (pinfunction "2_2") (pintype "passive"))
    )
    (net (code "85") (name "LINEIN_SW_R") (class "Default")
      (node (ref "J5") (pin "3") (pinfunction "3_3") (pintype "passive"))
      (node (ref "R17") (pin "2") (pinfunction "2_2") (pintype "passive"))
    )
    (net (code "86") (name "Net-(C3-Pad1)") (class "Default")
      (node (ref "C3") (pin "1") (pinfunction "1_1") (pintype "passive"))
      (node (ref "R2") (pin "1") (pinfunction "1_1") (pintype "passive"))
    )
    (net (code "87") (name "Net-(C25-Pad1)") (class "Default")
      (node (ref "C25") (pin "1") (pinfunction "1_1") (pintype "passive"))
      (node (ref "Q2") (pin "2") (pinfunction "2_2") (pintype "passive"))
      (node (ref "R20") (pin "2") (pinfunction "2_2") (pintype "passive"))
    )
    (net (code "88") (name "Net-(C34-Pad2)") (class "Default")
      (node (ref "C34") (pin "2") (pinfunction "2_2") (pintype "passive"))
      (node (ref "R21") (pin "2") (pinfunction "2_2") (pintype "passive"))
    )
    (net (code "89") (name "Net-(C35-Pad-)") (class "Default")
      (node (ref "C35") (pin "-") (pinfunction "-_-") (pintype "passive"))
      (node (ref "R22") (pin "2") (pinfunction "2_2") (pintype "passive"))
    )
    (net (code "90") (name "Net-(C37-Pad-)") (class "Default")
      (node (ref "C37") (pin "-") (pinfunction "-_-") (pintype "passive"))
      (node (ref "R23") (pin "2") (pinfunction "2_2") (pintype "passive"))
    )
    (net (code "91") (name "Net-(C39-Pad-)") (class "Default")
      (node (ref "C39") (pin "-") (pinfunction "-_-") (pintype "passive"))
      (node (ref "R24") (pin "2") (pinfunction "2_2") (pintype "passive"))
    )
    (net (code "92") (name "Net-(C41-Pad-)") (class "Default")
      (node (ref "C41") (pin "-") (pinfunction "-_-") (pintype "passive"))
      (node (ref "R25") (pin "2") (pinfunction "2_2") (pintype "passive"))
    )
    (net (code "93") (name "Net-(C55-Pad2)") (class "Default")
      (node (ref "C55") (pin "2") (pinfunction "2_2") (pintype "passive"))
      (node (ref "R34") (pin "1") (pinfunction "1_1") (pintype "passive"))
    )
    (net (code "94") (name "Net-(C58-Pad1)") (class "Default")
      (node (ref "C58") (pin "1") (pinfunction "1_1") (pintype "passive"))
      (node (ref "R36") (pin "2") (pinfunction "2_2") (pintype "passive"))
    )
    (net (code "95") (name "Net-(C59-Pad1)") (class "Default")
      (node (ref "C59") (pin "1") (pinfunction "1_1") (pintype "passive"))
      (node (ref "R35") (pin "2") (pinfunction "2_2") (pintype "passive"))
    )
    (net (code "96") (name "Net-(C61-Pad2)") (class "Default")
      (node (ref "C61") (pin "2") (pinfunction "2_2") (pintype "passive"))
      (node (ref "R37") (pin "1") (pinfunction "1_1") (pintype "passive"))
    )
    (net (code "97") (name "Net-(C65-Pad1)") (class "Default")
      (node (ref "C65") (pin "1") (pinfunction "1_1") (pintype "passive"))
      (node (ref "R38") (pin "2") (pinfunction "2_2") (pintype "passive"))
    )
    (net (code "98") (name "Net-(C66-Pad1)") (class "Default")
      (node (ref "C66") (pin "1") (pinfunction "1_1") (pintype "passive"))
      (node (ref "R39") (pin "2") (pinfunction "2_2") (pintype "passive"))
    )
    (net (code "99") (name "Net-(C79-Pad2)") (class "Default")
      (node (ref "C79") (pin "2") (pinfunction "2_2") (pintype "passive"))
      (node (ref "R48") (pin "1") (pinfunction "1_1") (pintype "passive"))
    )
    (net (code "100") (name "Net-(C82-Pad1)") (class "Default")
      (node (ref "C82") (pin "1") (pinfunction "1_1") (pintype "passive"))
      (node (ref "R50") (pin "2") (pinfunction "2_2") (pintype "passive"))
    )
    (net (code "101") (name "Net-(C83-Pad1)") (class "Default")
      (node (ref "C83") (pin "1") (pinfunction "1_1") (pintype "passive"))
      (node (ref "R49") (pin "2") (pinfunction "2_2") (pintype "passive"))
    )
    (net (code "102") (name "Net-(C85-Pad2)") (class "Default")
      (node (ref "C85") (pin "2") (pinfunction "2_2") (pintype "passive"))
      (node (ref "R51") (pin "1") (pinfunction "1_1") (pintype "passive"))
    )
    (net (code "103") (name "Net-(C89-Pad1)") (class "Default")
      (node (ref "C89") (pin "1") (pinfunction "1_1") (pintype "passive"))
      (node (ref "R52") (pin "2") (pinfunction "2_2") (pintype "passive"))
    )
    (net (code "104") (name "Net-(C90-Pad1)") (class "Default")
      (node (ref "C90") (pin "1") (pinfunction "1_1") (pintype "passive"))
      (node (ref "R53") (pin "2") (pinfunction "2_2") (pintype "passive"))
    )
    (net (code "105") (name "Net-(JP1-Pad1)") (class "Default")
      (node (ref "JP1") (pin "1") (pinfunction "1_1") (pintype "passive"))
      (node (ref "R31") (pin "1") (pinfunction "1_1") (pintype "passive"))
      (node (ref "R32") (pin "2") (pinfunction "2_2") (pintype "passive"))
    )
    (net (code "106") (name "Net-(JP2-Pad1)") (class "Default")
      (node (ref "JP2") (pin "1") (pinfunction "1_1") (pintype "passive"))
      (node (ref "R32") (pin "1") (pinfunction "1_1") (pintype "passive"))
      (node (ref "R33") (pin "2") (pinfunction "2_2") (pintype "passive"))
    )
    (net (code "107") (name "Net-(JP5-Pad1)") (class "Default")
      (node (ref "JP5") (pin "1") (pinfunction "1_1") (pintype "passive"))
      (node (ref "R45") (pin "1") (pinfunction "1_1") (pintype "passive"))
      (node (ref "R46") (pin "2") (pinfunction "2_2") (pintype "passive"))
    )
    (net (code "108") (name "Net-(JP6-Pad1)") (class "Default")
      (node (ref "JP6") (pin "1") (pinfunction "1_1") (pintype "passive"))
      (node (ref "R46") (pin "1") (pinfunction "1_1") (pintype "passive"))
      (node (ref "R47") (pin "2") (pinfunction "2_2") (pintype "passive"))
    )
    (net (code "109") (name "Net-(L2-1)") (class "Default")
      (node (ref "L2") (pin "P$1") (pinfunction "1_P$1") (pintype "passive"))
      (node (ref "REG2") (pin "2") (pinfunction "SW_2") (pintype "power_in"))
    )
    (net (code "110") (name "Net-(REG1-BOOT)") (class "Default")
      (node (ref "C5") (pin "1") (pinfunction "1_1") (pintype "passive"))
      (node (ref "REG1") (pin "1") (pinfunction "BOOT_1") (pintype "bidirectional"))
    )
    (net (code "111") (name "Net-(REG1-COMP)") (class "Default")
      (node (ref "C4") (pin "1") (pinfunction "1_1") (pintype "passive"))
      (node (ref "R2") (pin "2") (pinfunction "2_2") (pintype "passive"))
      (node (ref "REG1") (pin "6") (pinfunction "COMP_6") (pintype "bidirectional"))
    )
    (net (code "112") (name "Net-(REG1-FB)") (class "Default")
      (node (ref "R3") (pin "1") (pinfunction "1_1") (pintype "passive"))
      (node (ref "R4") (pin "2") (pinfunction "2_2") (pintype "passive"))
      (node (ref "REG1") (pin "5") (pinfunction "FB_5") (pintype "bidirectional"))
    )
    (net (code "113") (name "Net-(REG1-RT_CLK)") (class "Default")
      (node (ref "R1") (pin "2") (pinfunction "2_2") (pintype "passive"))
      (node (ref "REG1") (pin "4") (pinfunction "RT_CLK_4") (pintype "bidirectional"))
    )
    (net (code "114") (name "Net-(REG2-FB)") (class "Default")
      (node (ref "R6") (pin "2") (pinfunction "2_2") (pintype "passive"))
      (node (ref "R7") (pin "1") (pinfunction "1_1") (pintype "passive"))
      (node (ref "REG2") (pin "5") (pinfunction "FB_5") (pintype "input"))
    )
    (net (code "115") (name "Net-(REG2-PG)") (class "Default")
      (node (ref "R5") (pin "1") (pinfunction "1_1") (pintype "passive"))
      (node (ref "REG2") (pin "7") (pinfunction "PG_7") (pintype "open_collector"))
    )
    (net (code "116") (name "Net-(REG2-SS_TR)") (class "Default")
      (node (ref "C8") (pin "2") (pinfunction "2_2") (pintype "passive"))
      (node (ref "REG2") (pin "9") (pinfunction "SS_TR_9") (pintype "input"))
    )
    (net (code "117") (name "Net-(U1A-ADC0)") (class "Default")
      (node (ref "R17") (pin "1") (pinfunction "1_1") (pintype "passive"))
      (node (ref "U1") (pin "2") (pinfunction "ADC0_2") (pintype "input"))
    )
    (net (code "118") (name "Net-(U1A-ADC1)") (class "Default")
      (node (ref "R19") (pin "1") (pinfunction "1_1") (pintype "passive"))
      (node (ref "U1") (pin "4") (pinfunction "ADC1_4") (pintype "input"))
    )
    (net (code "119") (name "Net-(U1A-ADC_RES)") (class "Default")
      (node (ref "R18") (pin "1") (pinfunction "1_1") (pintype "passive"))
      (node (ref "U1") (pin "3") (pinfunction "ADC_RES_3") (pintype "input"))
    )
    (net (code "120") (name "Net-(U1A-CM)") (class "Default")
      (node (ref "C31") (pin "2") (pinfunction "2_2") (pintype "passive"))
      (node (ref "C32") (pin "2") (pinfunction "2_2") (pintype "passive"))
      (node (ref "U1") (pin "40") (pinfunction "CM_40") (pintype "output"))
    )
    (net (code "121") (name "Net-(U1A-FILTA)") (class "Default")
      (node (ref "C29") (pin "2") (pinfunction "2_2") (pintype "passive"))
      (node (ref "C30") (pin "2") (pinfunction "2_2") (pintype "passive"))
      (node (ref "U1") (pin "47") (pinfunction "FILTA_47") (pintype "output"))
    )
    (net (code "122") (name "Net-(U1A-FILTD)") (class "Default")
      (node (ref "C27") (pin "2") (pinfunction "2_2") (pintype "passive"))
      (node (ref "C28") (pin "2") (pinfunction "2_2") (pintype "passive"))
      (node (ref "U1") (pin "41") (pinfunction "FILTD_41") (pintype "output"))
    )
    (net (code "123") (name "Net-(U1A-PLL_LF)") (class "Default")
      (node (ref "C33") (pin "1") (pinfunction "1_1") (pintype "passive"))
      (node (ref "C34") (pin "1") (pinfunction "1_1") (pintype "passive"))
      (node (ref "U1") (pin "35") (pinfunction "PLL_LF_35") (pintype "output"))
    )
    (net (code "124") (name "Net-(U2A-DIAG)") (class "Default")
      (node (ref "R29") (pin "1") (pinfunction "1_1") (pintype "passive"))
      (node (ref "U2") (pin "28") (pinfunction "DIAG_28") (pintype "passive"))
    )
    (net (code "125") (name "Net-(U2A-SVCC)") (class "Default")
      (node (ref "C43") (pin "2") (pinfunction "2_2") (pintype "passive"))
      (node (ref "U2") (pin "35") (pinfunction "SVCC_35") (pintype "passive"))
    )
    (net (code "126") (name "Net-(U2A-SVR)") (class "Default")
      (node (ref "C44") (pin "1") (pinfunction "1_1") (pintype "passive"))
      (node (ref "U2") (pin "29") (pinfunction "SVR_29") (pintype "passive"))
    )
    (net (code "127") (name "Net-(U3A-DIAG)") (class "Default")
      (node (ref "R43") (pin "1") (pinfunction "1_1") (pintype "passive"))
      (node (ref "U3") (pin "28") (pinfunction "DIAG_28") (pintype "passive"))
    )
    (net (code "128") (name "Net-(U3A-SVCC)") (class "Default")
      (node (ref "C67") (pin "2") (pinfunction "2_2") (pintype "passive"))
      (node (ref "U3") (pin "35") (pinfunction "SVCC_35") (pintype "passive"))
    )
    (net (code "129") (name "Net-(U3A-SVR)") (class "Default")
      (node (ref "C68") (pin "1") (pinfunction "1_1") (pintype "passive"))
      (node (ref "U3") (pin "29") (pinfunction "SVR_29") (pintype "passive"))
    )
    (net (code "130") (name "OUTA_N") (class "Default")
      (node (ref "C62") (pin "2") (pinfunction "2_2") (pintype "passive"))
      (node (ref "C64") (pin "1") (pinfunction "1_1") (pintype "passive"))
      (node (ref "L6") (pin "P$2") (pinfunction "2_P$2") (pintype "passive"))
      (node (ref "OUT_A_-") (pin "1") (pinfunction "P_1") (pintype "passive"))
      (node (ref "R39") (pin "1") (pinfunction "1_1") (pintype "passive"))
    )
    (net (code "131") (name "OUTA_P") (class "Default")
      (node (ref "C62") (pin "1") (pinfunction "1_1") (pintype "passive"))
      (node (ref "C63") (pin "2") (pinfunction "2_2") (pintype "passive"))
      (node (ref "L5") (pin "P$2") (pinfunction "2_P$2") (pintype "passive"))
      (node (ref "OUT_A_+") (pin "1") (pinfunction "P_1") (pintype "passive"))
      (node (ref "R38") (pin "1") (pinfunction "1_1") (pintype "passive"))
    )
    (net (code "132") (name "OUTB_N") (class "Default")
      (node (ref "C57") (pin "1") (pinfunction "1_1") (pintype "passive"))
      (node (ref "C60") (pin "2") (pinfunction "2_2") (pintype "passive"))
      (node (ref "L4") (pin "P$2") (pinfunction "2_P$2") (pintype "passive"))
      (node (ref "OUT_B_-") (pin "1") (pinfunction "P_1") (pintype "passive"))
      (node (ref "R35") (pin "1") (pinfunction "1_1") (pintype "passive"))
    )
    (net (code "133") (name "OUTB_P") (class "Default")
      (node (ref "C56") (pin "2") (pinfunction "2_2") (pintype "passive"))
      (node (ref "C60") (pin "1") (pinfunction "1_1") (pintype "passive"))
      (node (ref "L3") (pin "P$2") (pinfunction "2_P$2") (pintype "passive"))
      (node (ref "OUT_B_+") (pin "1") (pinfunction "P_1") (pintype "passive"))
      (node (ref "R36") (pin "1") (pinfunction "1_1") (pintype "passive"))
    )
    (net (code "134") (name "OUTC_N") (class "Default")
      (node (ref "C86") (pin "2") (pinfunction "2_2") (pintype "passive"))
      (node (ref "C88") (pin "1") (pinfunction "1_1") (pintype "passive"))
      (node (ref "L10") (pin "P$2") (pinfunction "2_P$2") (pintype "passive"))
      (node (ref "OUT_C_-") (pin "1") (pinfunction "P_1") (pintype "passive"))
      (node (ref "R53") (pin "1") (pinfunction "1_1") (pintype "passive"))
    )
    (net (code "135") (name "OUTC_P") (class "Default")
      (node (ref "C86") (pin "1") (pinfunction "1_1") (pintype "passive"))
      (node (ref "C87") (pin "2") (pinfunction "2_2") (pintype "passive"))
      (node (ref "L9") (pin "P$2") (pinfunction "2_P$2") (pintype "passive"))
      (node (ref "OUT_C_+") (pin "1") (pinfunction "P_1") (pintype "passive"))
      (node (ref "R52") (pin "1") (pinfunction "1_1") (pintype "passive"))
    )
    (net (code "136") (name "OUTD_N") (class "Default")
      (node (ref "C81") (pin "1") (pinfunction "1_1") (pintype "passive"))
      (node (ref "C84") (pin "2") (pinfunction "2_2") (pintype "passive"))
      (node (ref "L8") (pin "P$2") (pinfunction "2_P$2") (pintype "passive"))
      (node (ref "OUT_D_-") (pin "1") (pinfunction "P_1") (pintype "passive"))
      (node (ref "R49") (pin "1") (pinfunction "1_1") (pintype "passive"))
    )
    (net (code "137") (name "OUTD_P") (class "Default")
      (node (ref "C80") (pin "2") (pinfunction "2_2") (pintype "passive"))
      (node (ref "C84") (pin "1") (pinfunction "1_1") (pintype "passive"))
      (node (ref "L7") (pin "P$2") (pinfunction "2_P$2") (pintype "passive"))
      (node (ref "OUT_D_+") (pin "1") (pinfunction "P_1") (pintype "passive"))
      (node (ref "R50") (pin "1") (pinfunction "1_1") (pintype "passive"))
    )
    (net (code "138") (name "P12V_EN") (class "Default")
      (node (ref "REG1") (pin "3") (pinfunction "EN_3") (pintype "bidirectional"))
    )
    (net (code "139") (name "POT0") (class "Default")
      (node (ref "R9") (pin "S") (pinfunction "S_S") (pintype "passive"))
      (node (ref "U1") (pin "26") (pinfunction "MP9_26") (pintype "bidirectional"))
    )
    (net (code "140") (name "POT1") (class "Default")
      (node (ref "R10") (pin "S") (pinfunction "S_S") (pintype "passive"))
      (node (ref "U1") (pin "27") (pinfunction "MP8_27") (pintype "bidirectional"))
    )
    (net (code "141") (name "POT2") (class "Default")
      (node (ref "R11") (pin "S") (pinfunction "S_S") (pintype "passive"))
      (node (ref "U1") (pin "28") (pinfunction "MP3_28") (pintype "bidirectional"))
    )
    (net (code "142") (name "POT3") (class "Default")
      (node (ref "R12") (pin "S") (pinfunction "S_S") (pintype "passive"))
      (node (ref "U1") (pin "29") (pinfunction "MP2_29") (pintype "bidirectional"))
    )
    (net (code "143") (name "R12V_SW") (class "Default")
      (node (ref "C5") (pin "2") (pinfunction "2_2") (pintype "passive"))
      (node (ref "D1") (pin "2") (pinfunction "C_2") (pintype "passive"))
      (node (ref "L1") (pin "P$1") (pinfunction "1_P$1") (pintype "passive"))
      (node (ref "REG1") (pin "8") (pinfunction "SW_8") (pintype "bidirectional"))
    )
    (net (code "144") (name "V+") (class "Default")
      (node (ref "C1") (pin "+") (pinfunction "+_+") (pintype "passive"))
      (node (ref "C2") (pin "+") (pinfunction "+_+") (pintype "passive"))
      (node (ref "C49") (pin "+") (pinfunction "+_+") (pintype "passive"))
      (node (ref "C50") (pin "+") (pinfunction "+_+") (pintype "passive"))
      (node (ref "C51") (pin "1") (pinfunction "1_1") (pintype "passive"))
      (node (ref "C52") (pin "1") (pinfunction "1_1") (pintype "passive"))
      (node (ref "C53") (pin "1") (pinfunction "1_1") (pintype "passive"))
      (node (ref "C54") (pin "1") (pinfunction "1_1") (pintype "passive"))
      (node (ref "C7") (pin "1") (pinfunction "1_1") (pintype "passive"))
      (node (ref "C73") (pin "+") (pinfunction "+_+") (pintype "passive"))
      (node (ref "C74") (pin "+") (pinfunction "+_+") (pintype "passive"))
      (node (ref "C75") (pin "1") (pinfunction "1_1") (pintype "passive"))
      (node (ref "C76") (pin "1") (pinfunction "1_1") (pintype "passive"))
      (node (ref "C77") (pin "1") (pinfunction "1_1") (pintype "passive"))
      (node (ref "C78") (pin "1") (pinfunction "1_1") (pintype "passive"))
      (node (ref "REG1") (pin "2") (pinfunction "VIN_2") (pintype "bidirectional"))
      (node (ref "U$1") (pin "+") (pinfunction "VCC_+") (pintype "bidirectional"))
      (node (ref "U2") (pin "12") (pinfunction "PVCCA_2_12") (pintype "passive"))
      (node (ref "U2") (pin "13") (pinfunction "PVCCA_13") (pintype "passive"))
      (node (ref "U2") (pin "6") (pinfunction "PVCCB_2_6") (pintype "passive"))
      (node (ref "U2") (pin "7") (pinfunction "PVCCB_7") (pintype "passive"))
      (node (ref "U3") (pin "12") (pinfunction "PVCCA_2_12") (pintype "passive"))
      (node (ref "U3") (pin "13") (pinfunction "PVCCA_13") (pintype "passive"))
      (node (ref "U3") (pin "6") (pinfunction "PVCCB_2_6") (pintype "passive"))
      (node (ref "U3") (pin "7") (pinfunction "PVCCB_7") (pintype "passive"))
      (node (ref "VIN") (pin "1") (pinfunction "P_1") (pintype "passive"))
    )
    (net (code "145") (name "unconnected-(J1-D+-Pad3)") (class "Default")
      (node (ref "J1") (pin "3") (pinfunction "D+_3") (pintype "bidirectional"))
    )
    (net (code "146") (name "unconnected-(J1-D--Pad2)") (class "Default")
      (node (ref "J1") (pin "2") (pinfunction "D-_2") (pintype "bidirectional"))
    )
    (net (code "147") (name "unconnected-(J2-D+-Pad3)") (class "Default")
      (node (ref "J2") (pin "3") (pinfunction "D+_3") (pintype "bidirectional"))
    )
    (net (code "148") (name "unconnected-(J2-D--Pad2)") (class "Default")
      (node (ref "J2") (pin "2") (pinfunction "D-_2") (pintype "bidirectional"))
    )
    (net (code "149") (name "unconnected-(U1A-CLATCH{slash}WP-Pad21)") (class "Default")
      (node (ref "U1") (pin "21") (pinfunction "CLATCH/WP_21") (pintype "bidirectional"))
    )
  )
)
